# C-12_PWR_MEAS.net
KiCad netlist of a schematic drawn in Altium Designer
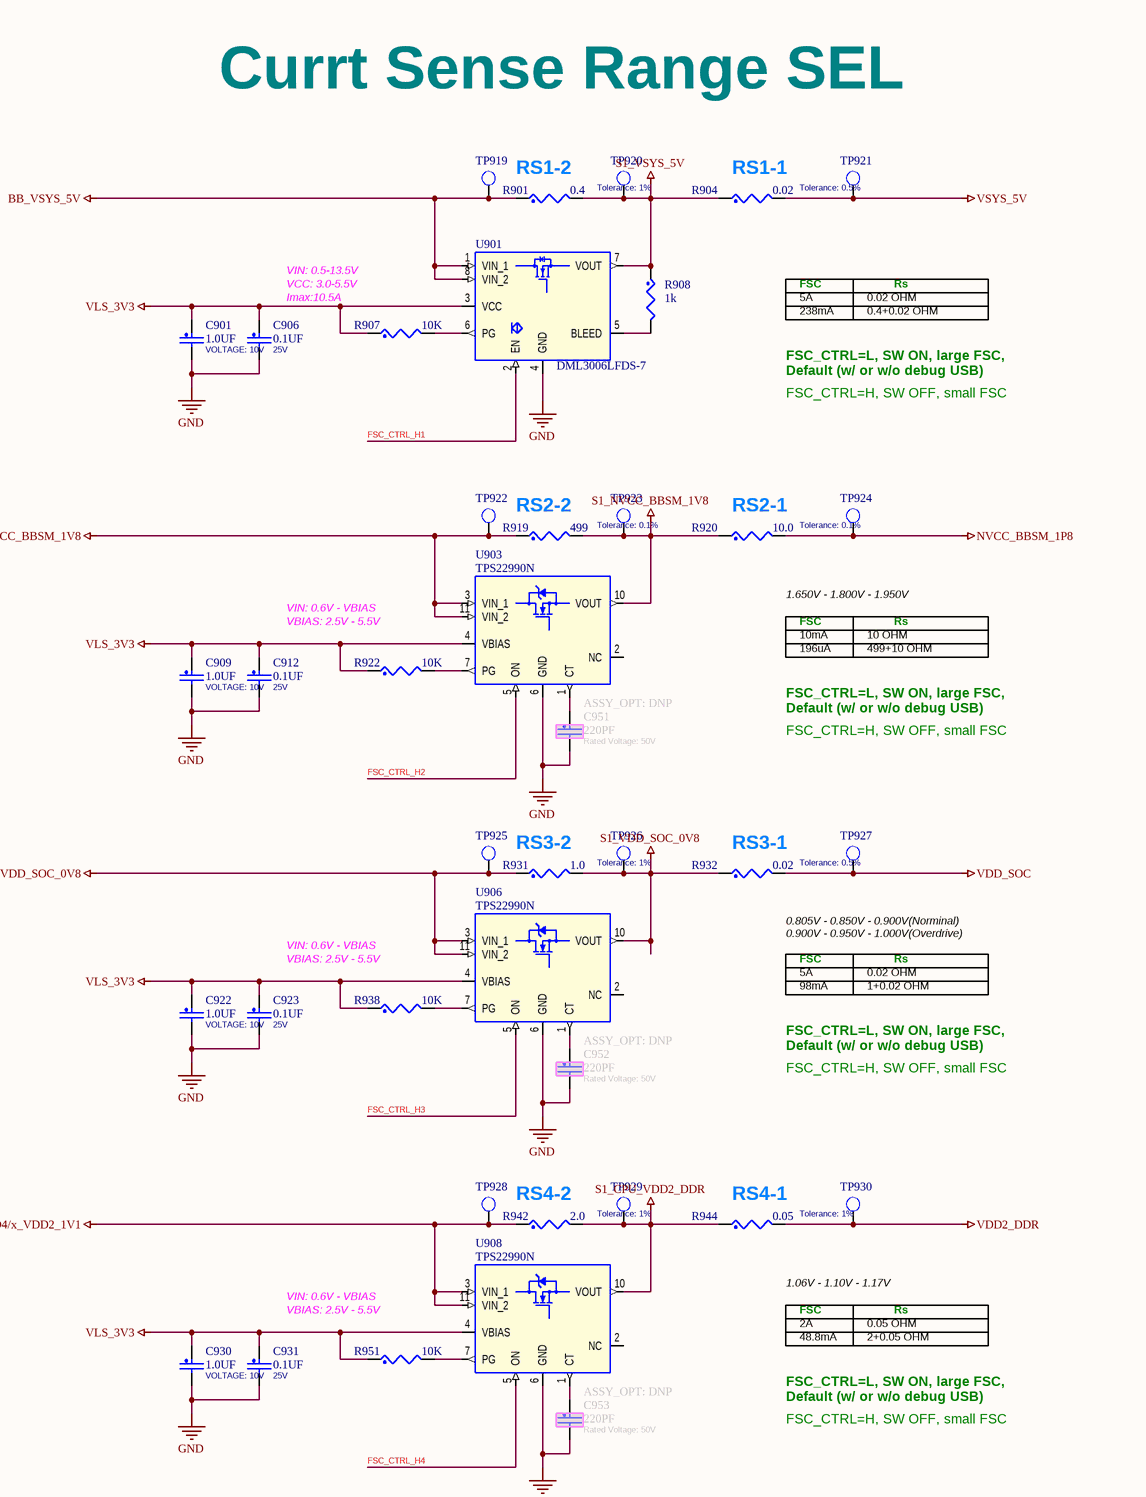
[diagram p0: C-12 PWR MEAS.SchDoc, top left]
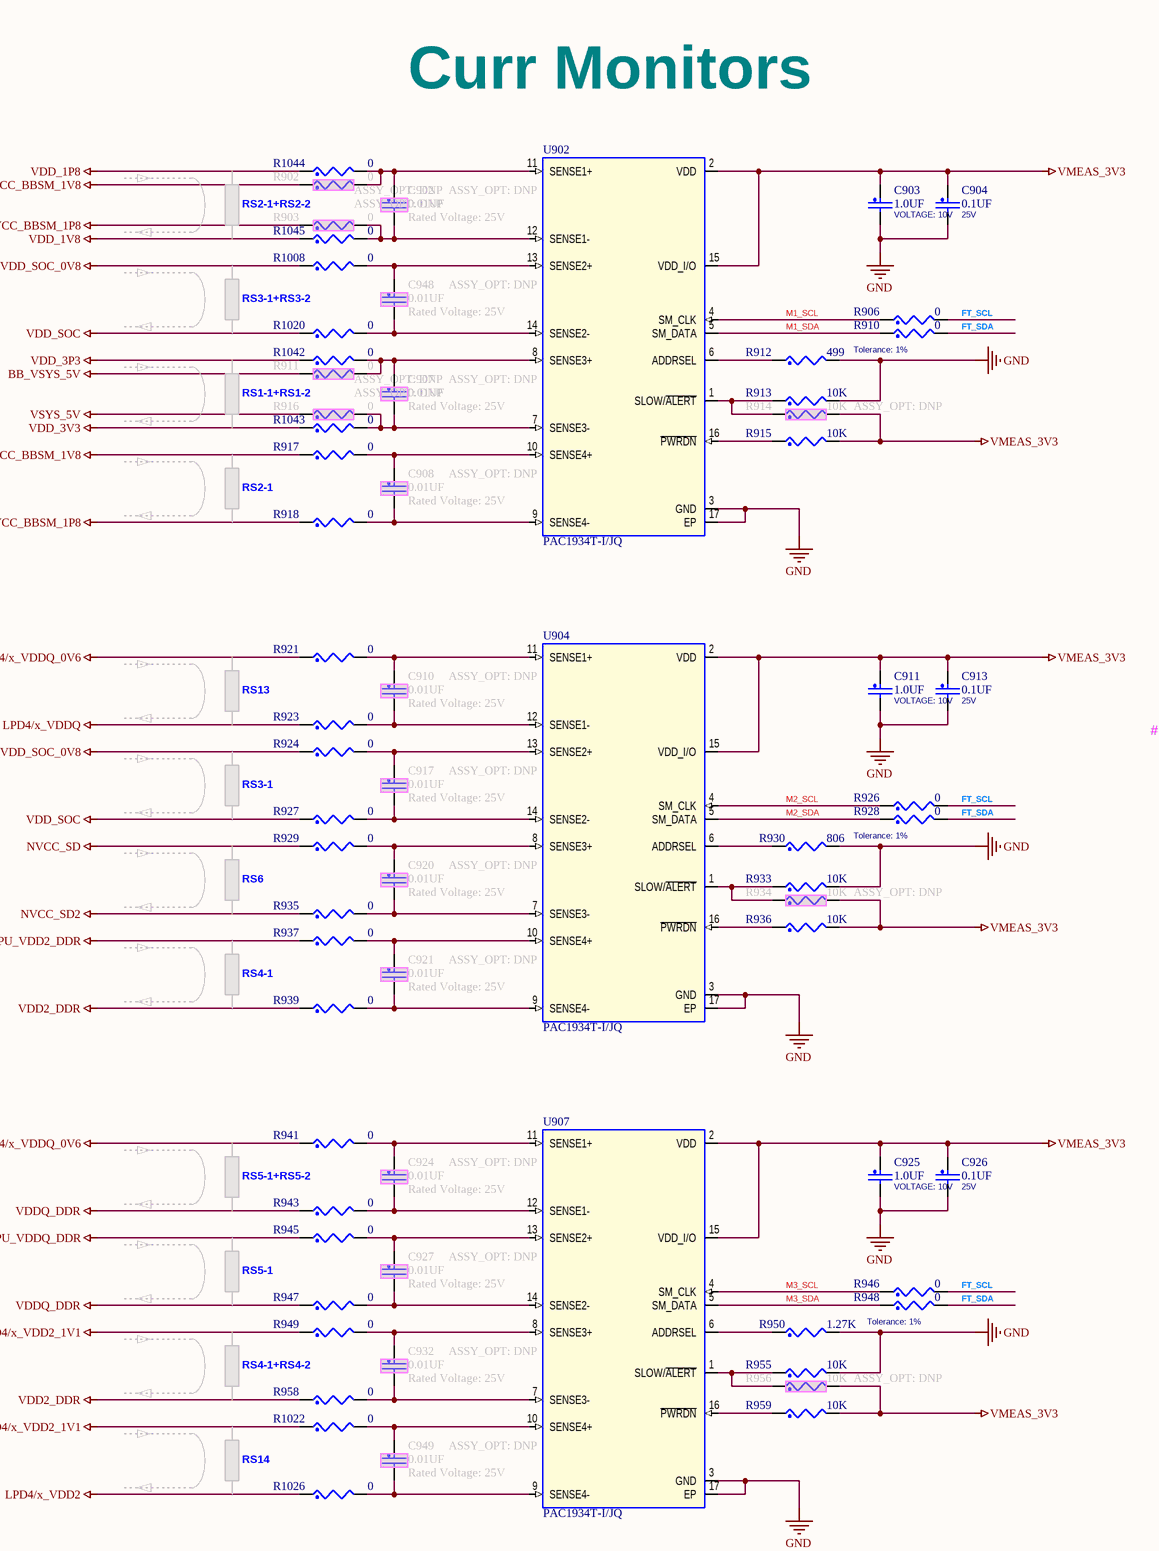
[diagram p1: C-12 PWR MEAS.SchDoc, top middle]
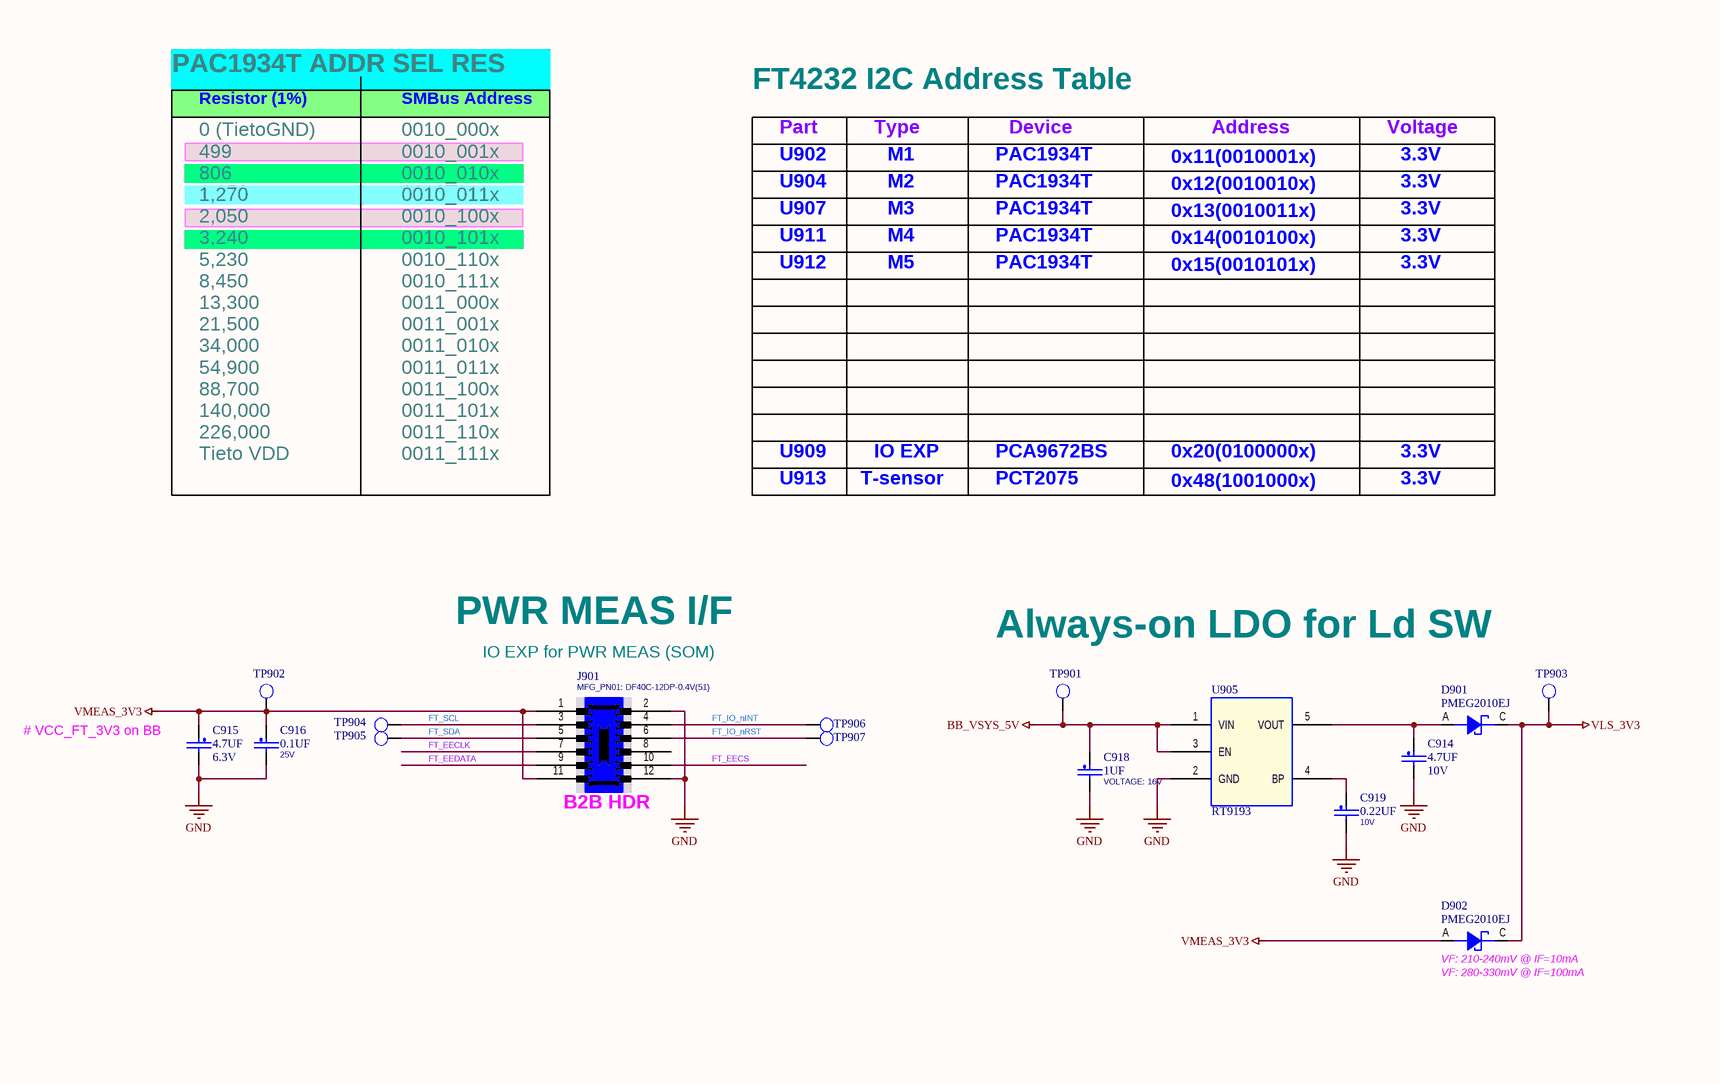
[diagram p2: C-12 PWR MEAS.SchDoc, top right]
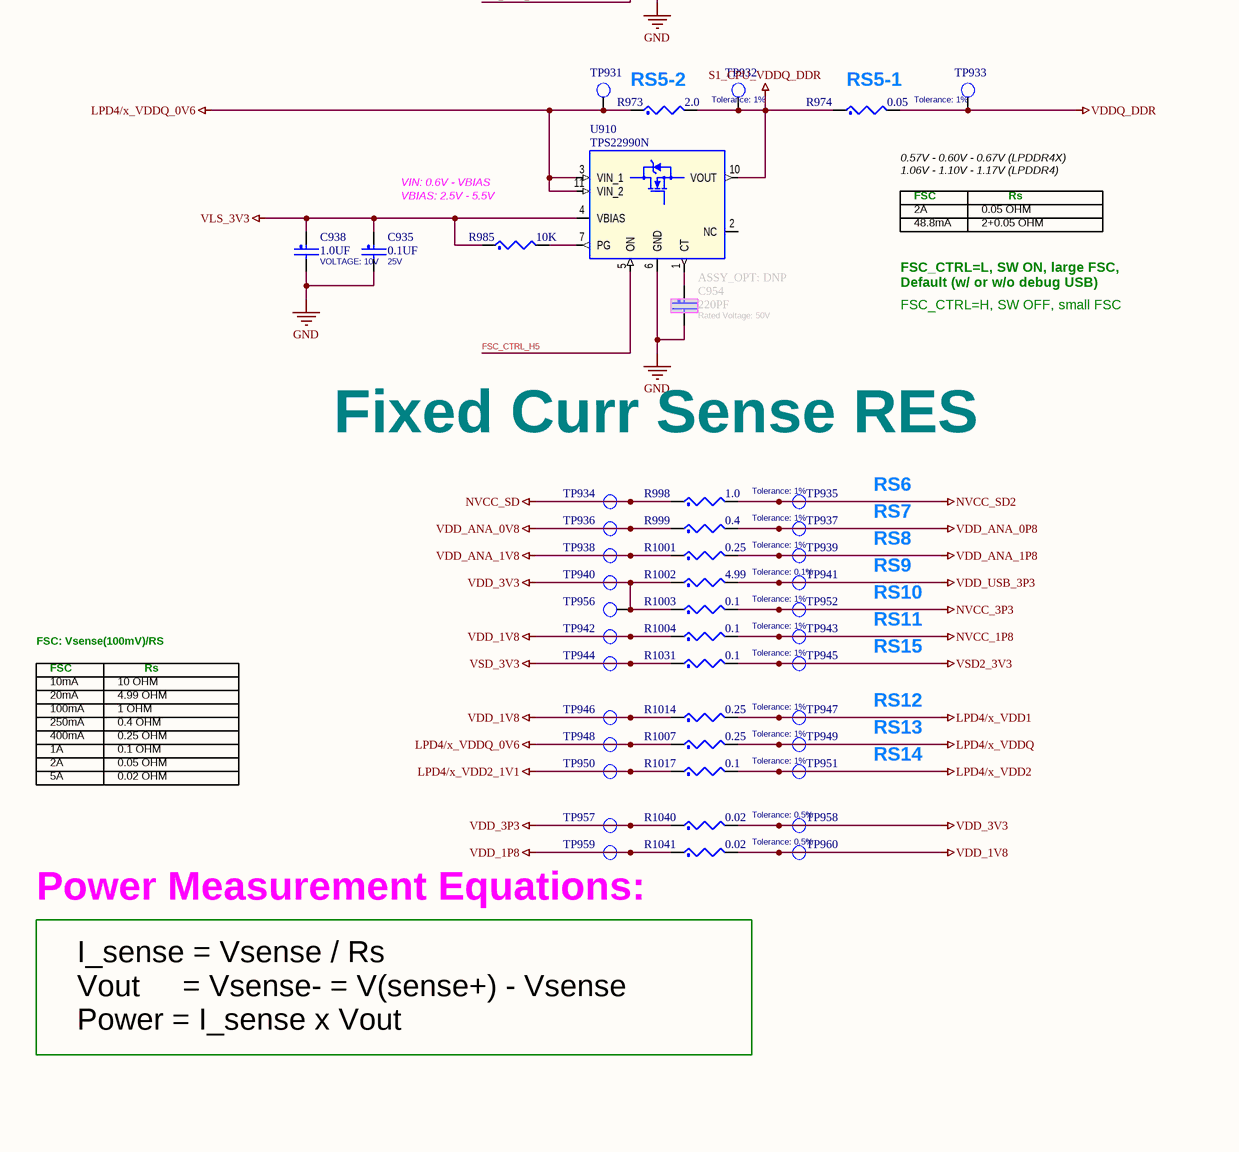
[diagram p3: C-12 PWR MEAS.SchDoc, bottom left]
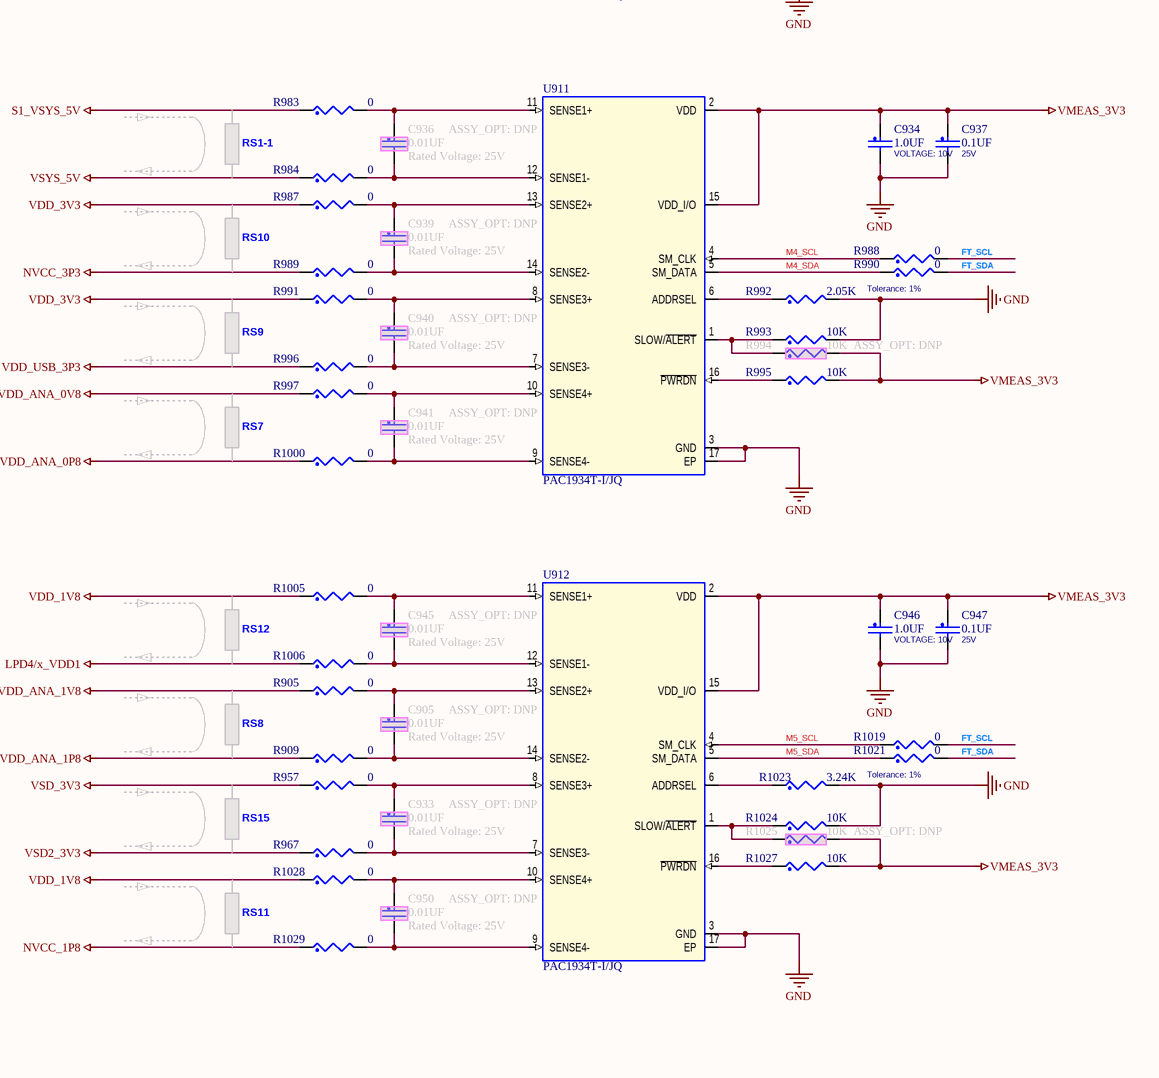
[diagram p4: C-12 PWR MEAS.SchDoc, bottom middle]
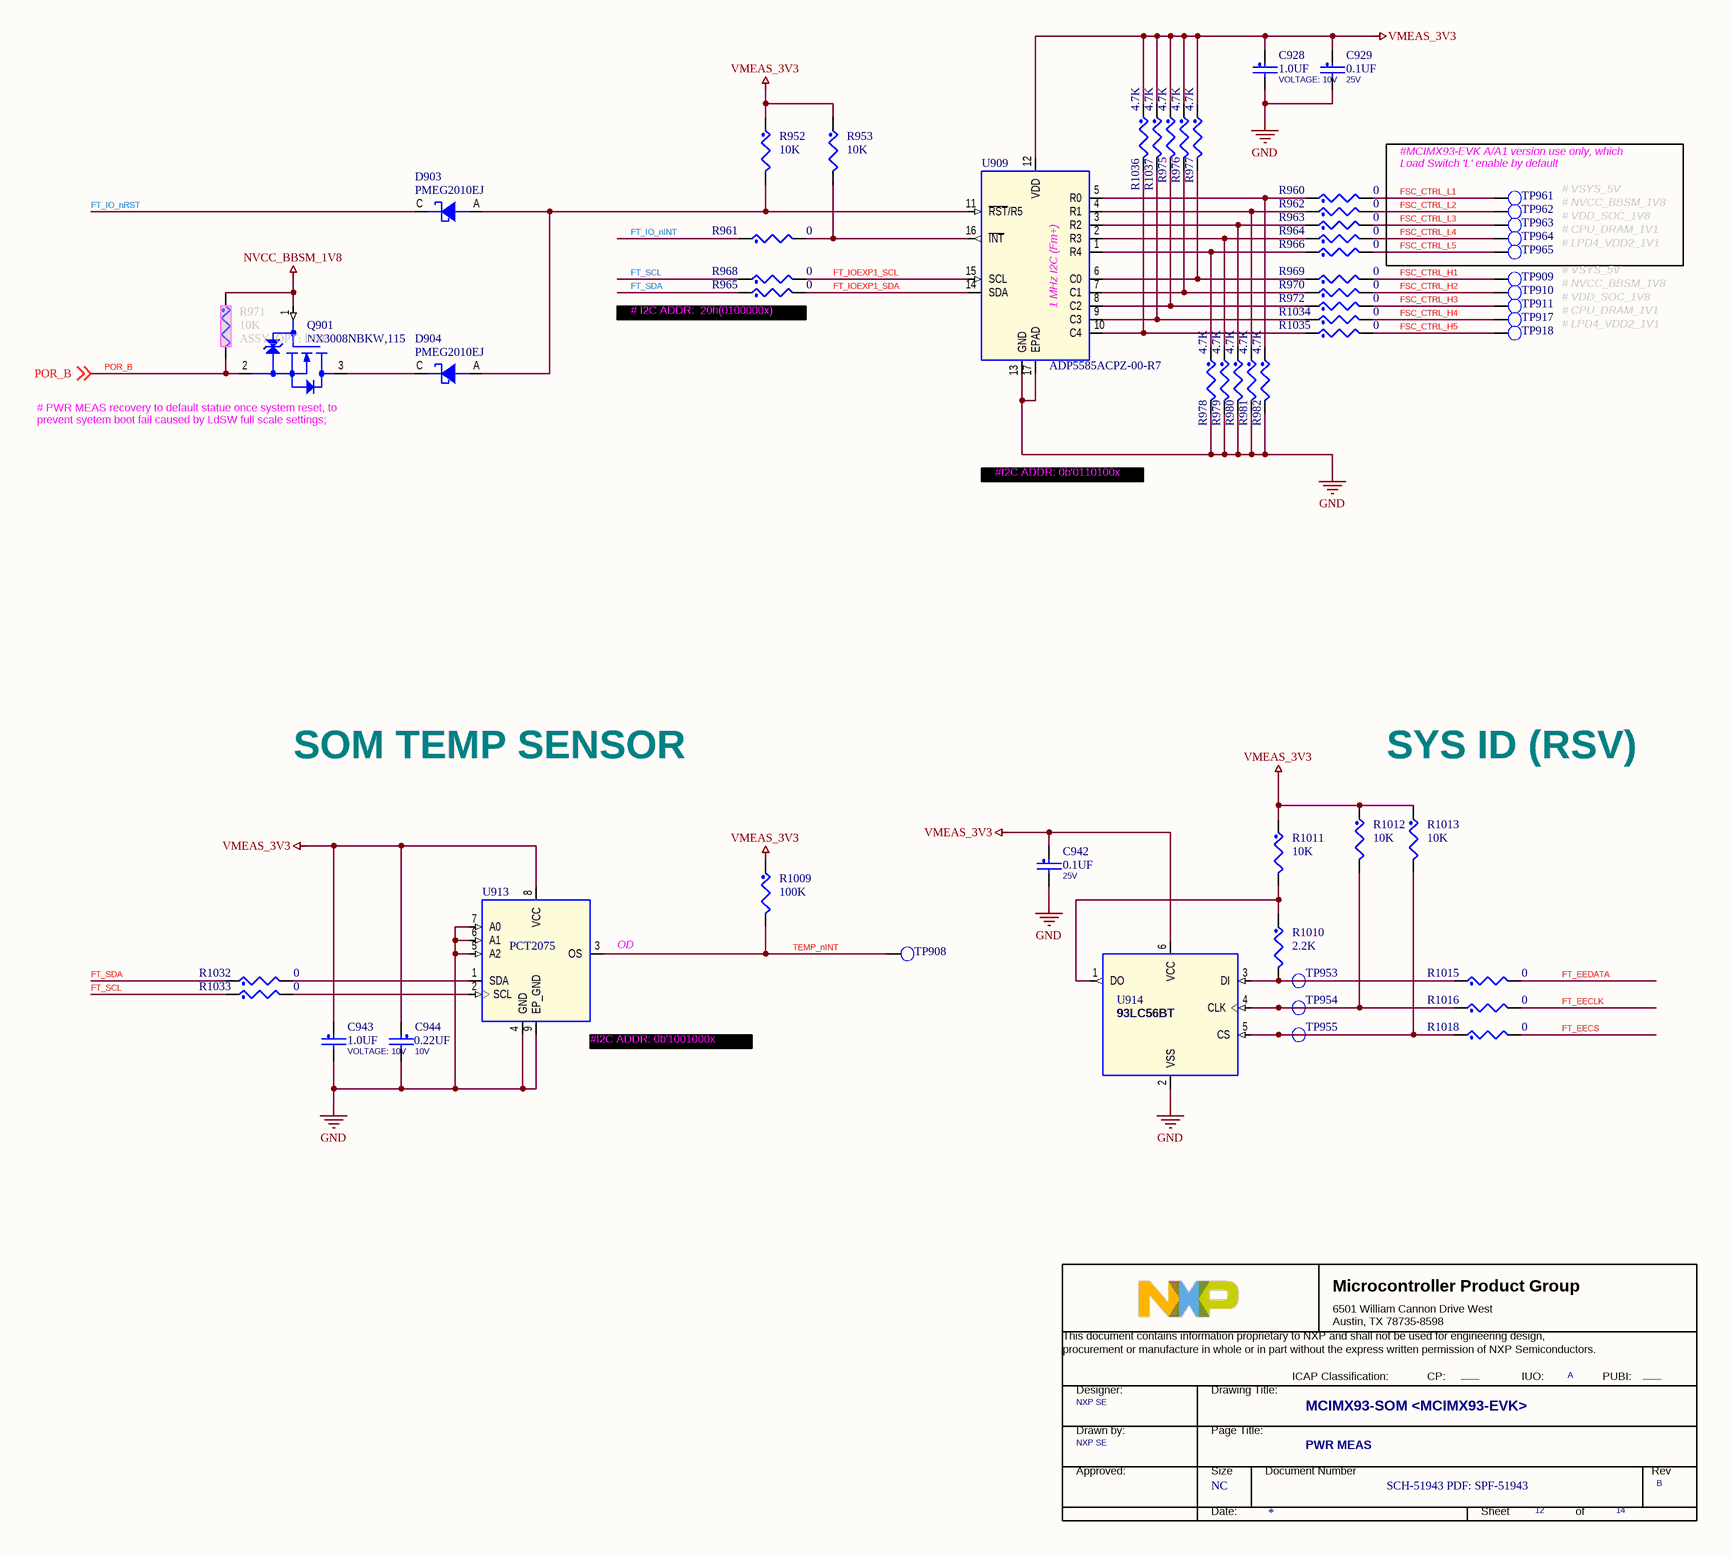
[diagram p5: C-12 PWR MEAS.SchDoc, bottom right]

(export (version "E")
  (design (tool "Eeschema 10.0.6"))
  (components
    (comp (ref "C901")
      (value "1.0UF")
      (footprint "0402_CC")
      (description "CAP CER 1.0UF 10V 10% X5R 0402")
      (fields (field (name "VOLTAGE") "10V"))
      (libsource (lib "*") (part "CAP_NP"))
    )
    (comp (ref "C902")
      (value "0.01UF")
      (footprint "CC0402_25")
      (description "CAP CER 0.01uF 25V 5% X7R 0402")
      (fields
        (field (name "ASSY_OPT") "DNP")
        (field (name "RATED VOLTAGE") "25V")
        (field (name "TOLERANCE") "5%")
      )
      (libsource (lib "*") (part "CAP_NP"))
    )
    (comp (ref "C903")
      (value "1.0UF")
      (footprint "0402_CC")
      (description "CAP CER 1.0UF 10V 10% X5R 0402")
      (fields (field (name "VOLTAGE") "10V"))
      (libsource (lib "*") (part "CAP_NP"))
    )
    (comp (ref "C904")
      (value "0.1UF")
      (footprint "0402_CC")
      (description "CAP CER 0.1UF 25V 10% X5R 0402")
      (fields (field (name "TOLERANCE") "10%") (field (name "VOLTAGE") "25V"))
      (libsource (lib "*") (part "CAP_NP"))
    )
    (comp (ref "C905")
      (value "0.01UF")
      (footprint "CC0402_25")
      (description "CAP CER 0.01uF 25V 5% X7R 0402")
      (fields
        (field (name "ASSY_OPT") "DNP")
        (field (name "RATED VOLTAGE") "25V")
        (field (name "TOLERANCE") "5%")
      )
      (libsource (lib "*") (part "CAP_NP"))
    )
    (comp (ref "C906")
      (value "0.1UF")
      (footprint "0402_CC")
      (description "CAP CER 0.1UF 25V 10% X5R 0402")
      (fields (field (name "TOLERANCE") "10%") (field (name "VOLTAGE") "25V"))
      (libsource (lib "*") (part "CAP_NP"))
    )
    (comp (ref "C907")
      (value "0.01UF")
      (footprint "CC0402_25")
      (description "CAP CER 0.01uF 25V 5% X7R 0402")
      (fields
        (field (name "ASSY_OPT") "DNP")
        (field (name "RATED VOLTAGE") "25V")
        (field (name "TOLERANCE") "5%")
      )
      (libsource (lib "*") (part "CAP_NP"))
    )
    (comp (ref "C908")
      (value "0.01UF")
      (footprint "CC0402_25")
      (description "CAP CER 0.01uF 25V 5% X7R 0402")
      (fields
        (field (name "ASSY_OPT") "DNP")
        (field (name "RATED VOLTAGE") "25V")
        (field (name "TOLERANCE") "5%")
      )
      (libsource (lib "*") (part "CAP_NP"))
    )
    (comp (ref "C909")
      (value "1.0UF")
      (footprint "0402_CC")
      (description "CAP CER 1.0UF 10V 10% X5R 0402")
      (fields (field (name "VOLTAGE") "10V"))
      (libsource (lib "*") (part "CAP_NP"))
    )
    (comp (ref "C910")
      (value "0.01UF")
      (footprint "CC0402_25")
      (description "CAP CER 0.01uF 25V 5% X7R 0402")
      (fields
        (field (name "ASSY_OPT") "DNP")
        (field (name "TOLERANCE") "5%")
        (field (name "RATED VOLTAGE") "25V")
      )
      (libsource (lib "*") (part "CAP_NP"))
    )
    (comp (ref "C911")
      (value "1.0UF")
      (footprint "0402_CC")
      (description "CAP CER 1.0UF 10V 10% X5R 0402")
      (fields (field (name "VOLTAGE") "10V"))
      (libsource (lib "*") (part "CAP_NP"))
    )
    (comp (ref "C912")
      (value "0.1UF")
      (footprint "0402_CC")
      (description "CAP CER 0.1UF 25V 10% X5R 0402")
      (fields (field (name "VOLTAGE") "25V") (field (name "TOLERANCE") "10%"))
      (libsource (lib "*") (part "CAP_NP"))
    )
    (comp (ref "C913")
      (value "0.1UF")
      (footprint "0402_CC")
      (description "CAP CER 0.1UF 25V 10% X5R 0402")
      (fields (field (name "VOLTAGE") "25V") (field (name "TOLERANCE") "10%"))
      (libsource (lib "*") (part "CAP_NP"))
    )
    (comp (ref "C914")
      (value "4.7UF")
      (footprint "cc0402_tol0p15")
      (description "CAP CER 4.7uF 10V 10% X5R 0402")
      (fields (field (name "TOLERANCE") "10%") (field (name "VOLTAGE") "10V"))
      (libsource (lib "*") (part "CAP_NP"))
    )
    (comp (ref "C915")
      (value "4.7UF")
      (footprint "cc0402_tol0p15")
      (description "CAP CER 4.7uF 10V 10% X5R 0402")
      (fields
        (field (name "VOLTAGE") "10V")
        (field (name "VOLTAGE RATING") "6.3V")
        (field (name "TOLERANCE") "10%")
      )
      (libsource (lib "*") (part "CAP_NP"))
    )
    (comp (ref "C916")
      (value "0.1UF")
      (footprint "0402_CC")
      (description "CAP CER 0.1UF 25V 10% X5R 0402")
      (fields (field (name "TOLERANCE") "10%") (field (name "VOLTAGE") "25V"))
      (libsource (lib "*") (part "CAP_NP"))
    )
    (comp (ref "C917")
      (value "0.01UF")
      (footprint "CC0402_25")
      (description "CAP CER 0.01uF 25V 5% X7R 0402")
      (fields
        (field (name "ASSY_OPT") "DNP")
        (field (name "TOLERANCE") "5%")
        (field (name "RATED VOLTAGE") "25V")
      )
      (libsource (lib "*") (part "CAP_NP"))
    )
    (comp (ref "C918")
      (value "1UF")
      (footprint "0402_CC")
      (description "CAP CER 1uF 16V 10% X5R 0402")
      (fields (field (name "VOLTAGE") "16V") (field (name "TOLERANCE") "10%"))
      (libsource (lib "*") (part "CAP_NP"))
    )
    (comp (ref "C919")
      (value "0.22UF")
      (footprint "0201_CC")
      (description "CAP CER 0.22UF 10V 20% X5R 0201")
      (fields (field (name "VOLTAGE") "10V") (field (name "TOLERANCE") "20%"))
      (libsource (lib "*") (part "CAP_NP"))
    )
    (comp (ref "C920")
      (value "0.01UF")
      (footprint "CC0402_25")
      (description "CAP CER 0.01uF 25V 5% X7R 0402")
      (fields
        (field (name "ASSY_OPT") "DNP")
        (field (name "TOLERANCE") "5%")
        (field (name "RATED VOLTAGE") "25V")
      )
      (libsource (lib "*") (part "CAP_NP"))
    )
    (comp (ref "C921")
      (value "0.01UF")
      (footprint "CC0402_25")
      (description "CAP CER 0.01uF 25V 5% X7R 0402")
      (fields
        (field (name "ASSY_OPT") "DNP")
        (field (name "TOLERANCE") "5%")
        (field (name "RATED VOLTAGE") "25V")
      )
      (libsource (lib "*") (part "CAP_NP"))
    )
    (comp (ref "C922")
      (value "1.0UF")
      (footprint "0402_CC")
      (description "CAP CER 1.0UF 10V 10% X5R 0402")
      (fields (field (name "VOLTAGE") "10V"))
      (libsource (lib "*") (part "CAP_NP"))
    )
    (comp (ref "C923")
      (value "0.1UF")
      (footprint "0402_CC")
      (description "CAP CER 0.1UF 25V 10% X5R 0402")
      (fields (field (name "VOLTAGE") "25V") (field (name "TOLERANCE") "10%"))
      (libsource (lib "*") (part "CAP_NP"))
    )
    (comp (ref "C924")
      (value "0.01UF")
      (footprint "CC0402_25")
      (description "CAP CER 0.01uF 25V 5% X7R 0402")
      (fields
        (field (name "ASSY_OPT") "DNP")
        (field (name "TOLERANCE") "5%")
        (field (name "RATED VOLTAGE") "25V")
      )
      (libsource (lib "*") (part "CAP_NP"))
    )
    (comp (ref "C925")
      (value "1.0UF")
      (footprint "0402_CC")
      (description "CAP CER 1.0UF 10V 10% X5R 0402")
      (fields (field (name "VOLTAGE") "10V"))
      (libsource (lib "*") (part "CAP_NP"))
    )
    (comp (ref "C926")
      (value "0.1UF")
      (footprint "0402_CC")
      (description "CAP CER 0.1UF 25V 10% X5R 0402")
      (fields (field (name "VOLTAGE") "25V") (field (name "TOLERANCE") "10%"))
      (libsource (lib "*") (part "CAP_NP"))
    )
    (comp (ref "C927")
      (value "0.01UF")
      (footprint "CC0402_25")
      (description "CAP CER 0.01uF 25V 5% X7R 0402")
      (fields
        (field (name "ASSY_OPT") "DNP")
        (field (name "TOLERANCE") "5%")
        (field (name "RATED VOLTAGE") "25V")
      )
      (libsource (lib "*") (part "CAP_NP"))
    )
    (comp (ref "C928")
      (value "1.0UF")
      (footprint "0402_CC")
      (description "CAP CER 1.0UF 10V 10% X5R 0402")
      (fields (field (name "VOLTAGE") "10V"))
      (libsource (lib "*") (part "CAP_NP"))
    )
    (comp (ref "C929")
      (value "0.1UF")
      (footprint "0402_CC")
      (description "CAP CER 0.1UF 25V 10% X5R 0402")
      (fields (field (name "VOLTAGE") "25V") (field (name "TOLERANCE") "10%"))
      (libsource (lib "*") (part "CAP_NP"))
    )
    (comp (ref "C930")
      (value "1.0UF")
      (footprint "0402_CC")
      (description "CAP CER 1.0UF 10V 10% X5R 0402")
      (fields (field (name "VOLTAGE") "10V"))
      (libsource (lib "*") (part "CAP_NP"))
    )
    (comp (ref "C931")
      (value "0.1UF")
      (footprint "0402_CC")
      (description "CAP CER 0.1UF 25V 10% X5R 0402")
      (fields (field (name "VOLTAGE") "25V") (field (name "TOLERANCE") "10%"))
      (libsource (lib "*") (part "CAP_NP"))
    )
    (comp (ref "C932")
      (value "0.01UF")
      (footprint "CC0402_25")
      (description "CAP CER 0.01uF 25V 5% X7R 0402")
      (fields
        (field (name "ASSY_OPT") "DNP")
        (field (name "TOLERANCE") "5%")
        (field (name "RATED VOLTAGE") "25V")
      )
      (libsource (lib "*") (part "CAP_NP"))
    )
    (comp (ref "C933")
      (value "0.01UF")
      (footprint "CC0402_25")
      (description "CAP CER 0.01uF 25V 5% X7R 0402")
      (fields
        (field (name "ASSY_OPT") "DNP")
        (field (name "TOLERANCE") "5%")
        (field (name "RATED VOLTAGE") "25V")
      )
      (libsource (lib "*") (part "CAP_NP"))
    )
    (comp (ref "C934")
      (value "1.0UF")
      (footprint "0402_CC")
      (description "CAP CER 1.0UF 10V 10% X5R 0402")
      (fields (field (name "VOLTAGE") "10V"))
      (libsource (lib "*") (part "CAP_NP"))
    )
    (comp (ref "C935")
      (value "0.1UF")
      (footprint "0402_CC")
      (description "CAP CER 0.1UF 25V 10% X5R 0402")
      (fields (field (name "VOLTAGE") "25V") (field (name "TOLERANCE") "10%"))
      (libsource (lib "*") (part "CAP_NP"))
    )
    (comp (ref "C936")
      (value "0.01UF")
      (footprint "CC0402_25")
      (description "CAP CER 0.01uF 25V 5% X7R 0402")
      (fields
        (field (name "ASSY_OPT") "DNP")
        (field (name "TOLERANCE") "5%")
        (field (name "RATED VOLTAGE") "25V")
      )
      (libsource (lib "*") (part "CAP_NP"))
    )
    (comp (ref "C937")
      (value "0.1UF")
      (footprint "0402_CC")
      (description "CAP CER 0.1UF 25V 10% X5R 0402")
      (fields (field (name "VOLTAGE") "25V") (field (name "TOLERANCE") "10%"))
      (libsource (lib "*") (part "CAP_NP"))
    )
    (comp (ref "C938")
      (value "1.0UF")
      (footprint "0402_CC")
      (description "CAP CER 1.0UF 10V 10% X5R 0402")
      (fields (field (name "VOLTAGE") "10V"))
      (libsource (lib "*") (part "CAP_NP"))
    )
    (comp (ref "C939")
      (value "0.01UF")
      (footprint "CC0402_25")
      (description "CAP CER 0.01uF 25V 5% X7R 0402")
      (fields
        (field (name "ASSY_OPT") "DNP")
        (field (name "TOLERANCE") "5%")
        (field (name "RATED VOLTAGE") "25V")
      )
      (libsource (lib "*") (part "CAP_NP"))
    )
    (comp (ref "C940")
      (value "0.01UF")
      (footprint "CC0402_25")
      (description "CAP CER 0.01uF 25V 5% X7R 0402")
      (fields
        (field (name "ASSY_OPT") "DNP")
        (field (name "TOLERANCE") "5%")
        (field (name "RATED VOLTAGE") "25V")
      )
      (libsource (lib "*") (part "CAP_NP"))
    )
    (comp (ref "C941")
      (value "0.01UF")
      (footprint "CC0402_25")
      (description "CAP CER 0.01uF 25V 5% X7R 0402")
      (fields
        (field (name "ASSY_OPT") "DNP")
        (field (name "TOLERANCE") "5%")
        (field (name "RATED VOLTAGE") "25V")
      )
      (libsource (lib "*") (part "CAP_NP"))
    )
    (comp (ref "C942")
      (value "0.1UF")
      (footprint "0402_CC")
      (description "CAP CER 0.1UF 25V 10% X5R 0402")
      (fields (field (name "TOLERANCE") "10%") (field (name "VOLTAGE") "25V"))
      (libsource (lib "*") (part "CAP_NP"))
    )
    (comp (ref "C943")
      (value "1.0UF")
      (footprint "0402_CC")
      (description "CAP CER 1.0UF 10V 10% X5R 0402")
      (fields (field (name "VOLTAGE") "10V"))
      (libsource (lib "*") (part "CAP_NP"))
    )
    (comp (ref "C944")
      (value "0.22UF")
      (footprint "0201_CC")
      (description "CAP CER 0.22UF 10V 20% X5R 0201")
      (fields (field (name "TOLERANCE") "20%") (field (name "VOLTAGE") "10V"))
      (libsource (lib "*") (part "CAP_NP"))
    )
    (comp (ref "C945")
      (value "0.01UF")
      (footprint "CC0402_25")
      (description "CAP CER 0.01uF 25V 5% X7R 0402")
      (fields
        (field (name "ASSY_OPT") "DNP")
        (field (name "TOLERANCE") "5%")
        (field (name "RATED VOLTAGE") "25V")
      )
      (libsource (lib "*") (part "CAP_NP"))
    )
    (comp (ref "C946")
      (value "1.0UF")
      (footprint "0402_CC")
      (description "CAP CER 1.0UF 10V 10% X5R 0402")
      (fields (field (name "VOLTAGE") "10V"))
      (libsource (lib "*") (part "CAP_NP"))
    )
    (comp (ref "C947")
      (value "0.1UF")
      (footprint "0402_CC")
      (description "CAP CER 0.1UF 25V 10% X5R 0402")
      (fields (field (name "VOLTAGE") "25V") (field (name "TOLERANCE") "10%"))
      (libsource (lib "*") (part "CAP_NP"))
    )
    (comp (ref "C948")
      (value "0.01UF")
      (footprint "CC0402_25")
      (description "CAP CER 0.01uF 25V 5% X7R 0402")
      (fields
        (field (name "ASSY_OPT") "DNP")
        (field (name "TOLERANCE") "5%")
        (field (name "RATED VOLTAGE") "25V")
      )
      (libsource (lib "*") (part "CAP_NP"))
    )
    (comp (ref "C949")
      (value "0.01UF")
      (footprint "CC0402_25")
      (description "CAP CER 0.01uF 25V 5% X7R 0402")
      (fields
        (field (name "ASSY_OPT") "DNP")
        (field (name "TOLERANCE") "5%")
        (field (name "RATED VOLTAGE") "25V")
      )
      (libsource (lib "*") (part "CAP_NP"))
    )
    (comp (ref "C950")
      (value "0.01UF")
      (footprint "CC0402_25")
      (description "CAP CER 0.01uF 25V 5% X7R 0402")
      (fields
        (field (name "ASSY_OPT") "DNP")
        (field (name "TOLERANCE") "5%")
        (field (name "RATED VOLTAGE") "25V")
      )
      (libsource (lib "*") (part "CAP_NP"))
    )
    (comp (ref "C951")
      (value "220PF")
      (footprint "0402_CC")
      (description "CAP CER 220PF 50V 5% C0G 0402")
      (fields
        (field (name "ASSY_OPT") "DNP")
        (field (name "RATED VOLTAGE") "50V")
        (field (name "TOLERANCE") "5%")
      )
      (libsource (lib "*") (part "CAP_NP"))
    )
    (comp (ref "C952")
      (value "220PF")
      (footprint "0402_CC")
      (description "CAP CER 220PF 50V 5% C0G 0402")
      (fields
        (field (name "ASSY_OPT") "DNP")
        (field (name "RATED VOLTAGE") "50V")
        (field (name "TOLERANCE") "5%")
      )
      (libsource (lib "*") (part "CAP_NP"))
    )
    (comp (ref "C953")
      (value "220PF")
      (footprint "0402_CC")
      (description "CAP CER 220PF 50V 5% C0G 0402")
      (fields
        (field (name "ASSY_OPT") "DNP")
        (field (name "RATED VOLTAGE") "50V")
        (field (name "TOLERANCE") "5%")
      )
      (libsource (lib "*") (part "CAP_NP"))
    )
    (comp (ref "C954")
      (value "220PF")
      (footprint "0402_CC")
      (description "CAP CER 220PF 50V 5% C0G 0402")
      (fields
        (field (name "ASSY_OPT") "DNP")
        (field (name "RATED VOLTAGE") "50V")
        (field (name "TOLERANCE") "5%")
      )
      (libsource (lib "*") (part "CAP_NP"))
    )
    (comp (ref "D901")
      (value "PMEG2010EJ")
      (footprint "sod323")
      (description "DIODE SCH SW 1A 20V AEC-Q101 SOD323")
      (fields (field (name "VOLTAGE") "20V"))
      (libsource (lib "*") (part "DIODE_SCHTKY"))
    )
    (comp (ref "D902")
      (value "PMEG2010EJ")
      (footprint "sod323")
      (description "DIODE SCH SW 1A 20V AEC-Q101 SOD323")
      (fields (field (name "VOLTAGE") "20V"))
      (libsource (lib "*") (part "DIODE_SCHTKY"))
    )
    (comp (ref "D903")
      (value "PMEG2010EJ")
      (footprint "sod323")
      (description "DIODE SCH SW 1A 20V AEC-Q101 SOD323")
      (fields (field (name "VOLTAGE") "20V"))
      (libsource (lib "*") (part "DIODE_SCHTKY"))
    )
    (comp (ref "D904")
      (value "PMEG2010EJ")
      (footprint "sod323")
      (description "DIODE SCH SW 1A 20V AEC-Q101 SOD323")
      (fields (field (name "VOLTAGE") "20V"))
      (libsource (lib "*") (part "DIODE_SCHTKY"))
    )
    (comp (ref "J901")
      (value "CON 2X6")
      (footprint "con12_0p4_4p12x2p05_sm")
      (description "CON 2X6 PLUG SHRD SMT 0.4MM SP 51H AU")
      (fields (field (name "MFG_PN01") "DF40C-12DP-0.4V(51)"))
      (libsource (lib "*") (part "CONN_HDR_6X2_A"))
    )
    (comp (ref "Q901")
      (value "NX3008NBKW,115")
      (footprint "sc70_3")
      (description "TRAN NMOS SW 30V 350mA AEC-Q101 SC-70")
      (libsource (lib "*") (part "NX3008NBKW_SOT323"))
    )
    (comp (ref "R901")
      (value "0.4")
      (footprint "RC0603_OV")
      (description "RES MF 0.4 OHM 1/10W 1% AEC-Q200 0603")
      (fields (field (name "TOLERANCE") "1%"))
      (libsource (lib "*") (part "RES"))
    )
    (comp (ref "R902")
      (value "0")
      (footprint "0402_CC")
      (description "RES MF ZERO OHM 1/16W 5% 0402")
      (fields
        (field (name "ASSY_OPT") "DNP")
        (field (name "VOLTAGE") "1/16W")
        (field (name "TOLERANCE") "5%")
      )
      (libsource (lib "*") (part "RES"))
    )
    (comp (ref "R903")
      (value "0")
      (footprint "0402_CC")
      (description "RES MF ZERO OHM 1/16W 5% 0402")
      (fields
        (field (name "ASSY_OPT") "DNP")
        (field (name "VOLTAGE") "1/16W")
        (field (name "TOLERANCE") "5%")
      )
      (libsource (lib "*") (part "RES"))
    )
    (comp (ref "R904")
      (value "0.02")
      (footprint "RC0805_OV")
      (description "RES MF 0.02OHM 1/4W 0.5% 0805")
      (fields (field (name "TOLERANCE") "0.5%"))
      (libsource (lib "*") (part "RES"))
    )
    (comp (ref "R905")
      (value "0")
      (footprint "0402_CC")
      (description "RES MF ZERO OHM 1/16W 5% 0402")
      (fields (field (name "VOLTAGE") "1/16W") (field (name "TOLERANCE") "5%"))
      (libsource (lib "*") (part "RES"))
    )
    (comp (ref "R906")
      (value "0")
      (footprint "0201_CC")
      (description "RES MF ZERO OHM 1/20W -- 0201")
      (libsource (lib "*") (part "RES"))
    )
    (comp (ref "R907")
      (value "10K")
      (footprint "0402_CC")
      (description "RES MF 10K 1/16W 5% 0402")
      (fields (field (name "TOLERANCE") "5%"))
      (libsource (lib "*") (part "RES"))
    )
    (comp (ref "R908")
      (value "1k")
      (footprint "RC0603_OV")
      (description "RES MF 1.0K 1/10W 5% 0603")
      (fields (field (name "TOLERANCE") "5%"))
      (libsource (lib "*") (part "RES"))
    )
    (comp (ref "R909")
      (value "0")
      (footprint "0402_CC")
      (description "RES MF ZERO OHM 1/16W 5% 0402")
      (fields (field (name "VOLTAGE") "1/16W") (field (name "TOLERANCE") "5%"))
      (libsource (lib "*") (part "RES"))
    )
    (comp (ref "R910")
      (value "0")
      (footprint "0201_CC")
      (description "RES MF ZERO OHM 1/20W -- 0201")
      (libsource (lib "*") (part "RES"))
    )
    (comp (ref "R911")
      (value "0")
      (footprint "0402_CC")
      (description "RES MF ZERO OHM 1/16W 5% 0402")
      (fields
        (field (name "ASSY_OPT") "DNP")
        (field (name "TOLERANCE") "5%")
        (field (name "VOLTAGE") "1/16W")
      )
      (libsource (lib "*") (part "RES"))
    )
    (comp (ref "R912")
      (value "499")
      (footprint "RC0402_25")
      (description "RES MF 499 OHM 1/16W 1% 0402")
      (fields (field (name "TOLERANCE") "1%"))
      (libsource (lib "*") (part "RES"))
    )
    (comp (ref "R913")
      (value "10K")
      (footprint "0402_CC")
      (description "RES MF 10K 1/16W 5% 0402")
      (fields (field (name "TOLERANCE") "5%"))
      (libsource (lib "*") (part "RES"))
    )
    (comp (ref "R914")
      (value "10K")
      (footprint "0402_CC")
      (description "RES MF 10K 1/16W 5% 0402")
      (fields (field (name "ASSY_OPT") "DNP") (field (name "TOLERANCE") "5%"))
      (libsource (lib "*") (part "RES"))
    )
    (comp (ref "R915")
      (value "10K")
      (footprint "0402_CC")
      (description "RES MF 10K 1/16W 5% 0402")
      (fields (field (name "TOLERANCE") "5%"))
      (libsource (lib "*") (part "RES"))
    )
    (comp (ref "R916")
      (value "0")
      (footprint "0402_CC")
      (description "RES MF ZERO OHM 1/16W 5% 0402")
      (fields
        (field (name "ASSY_OPT") "DNP")
        (field (name "VOLTAGE") "1/16W")
        (field (name "TOLERANCE") "5%")
      )
      (libsource (lib "*") (part "RES"))
    )
    (comp (ref "R917")
      (value "0")
      (footprint "0402_CC")
      (description "RES MF ZERO OHM 1/16W 5% 0402")
      (fields (field (name "VOLTAGE") "1/16W") (field (name "TOLERANCE") "5%"))
      (libsource (lib "*") (part "RES"))
    )
    (comp (ref "R918")
      (value "0")
      (footprint "0402_CC")
      (description "RES MF ZERO OHM 1/16W 5% 0402")
      (fields (field (name "VOLTAGE") "1/16W") (field (name "TOLERANCE") "5%"))
      (libsource (lib "*") (part "RES"))
    )
    (comp (ref "R919")
      (value "499")
      (footprint "RC0603_OV")
      (description "RES MF 499 OHM 1/10W 0.1% AEC-Q200 0603")
      (fields (field (name "TOLERANCE") "0.1%"))
      (libsource (lib "*") (part "RES"))
    )
    (comp (ref "R920")
      (value "10.0")
      (footprint "RC0603_OV")
      (description "RES MF 10 OHM 1/16W 0.1% 0603")
      (fields (field (name "TOLERANCE") "0.1%"))
      (libsource (lib "*") (part "RES"))
    )
    (comp (ref "R921")
      (value "0")
      (footprint "0402_CC")
      (description "RES MF ZERO OHM 1/16W 5% 0402")
      (fields (field (name "TOLERANCE") "5%") (field (name "VOLTAGE") "1/16W"))
      (libsource (lib "*") (part "RES"))
    )
    (comp (ref "R922")
      (value "10K")
      (footprint "0402_CC")
      (description "RES MF 10K 1/16W 5% 0402")
      (fields (field (name "TOLERANCE") "5%"))
      (libsource (lib "*") (part "RES"))
    )
    (comp (ref "R923")
      (value "0")
      (footprint "0402_CC")
      (description "RES MF ZERO OHM 1/16W 5% 0402")
      (fields (field (name "TOLERANCE") "5%") (field (name "VOLTAGE") "1/16W"))
      (libsource (lib "*") (part "RES"))
    )
    (comp (ref "R924")
      (value "0")
      (footprint "0402_CC")
      (description "RES MF ZERO OHM 1/16W 5% 0402")
      (fields (field (name "TOLERANCE") "5%") (field (name "VOLTAGE") "1/16W"))
      (libsource (lib "*") (part "RES"))
    )
    (comp (ref "R926")
      (value "0")
      (footprint "0201_CC")
      (description "RES MF ZERO OHM 1/20W -- 0201")
      (libsource (lib "*") (part "RES"))
    )
    (comp (ref "R927")
      (value "0")
      (footprint "0402_CC")
      (description "RES MF ZERO OHM 1/16W 5% 0402")
      (fields (field (name "TOLERANCE") "5%") (field (name "VOLTAGE") "1/16W"))
      (libsource (lib "*") (part "RES"))
    )
    (comp (ref "R928")
      (value "0")
      (footprint "0201_CC")
      (description "RES MF ZERO OHM 1/20W -- 0201")
      (libsource (lib "*") (part "RES"))
    )
    (comp (ref "R929")
      (value "0")
      (footprint "0402_CC")
      (description "RES MF ZERO OHM 1/16W 5% 0402")
      (fields (field (name "TOLERANCE") "5%") (field (name "VOLTAGE") "1/16W"))
      (libsource (lib "*") (part "RES"))
    )
    (comp (ref "R930")
      (value "806")
      (footprint "RC0402_25")
      (description "RES TF 806 OHM 1% 1/10W AEC-Q200 0402")
      (fields (field (name "TOLERANCE") "1%"))
      (libsource (lib "*") (part "RES"))
    )
    (comp (ref "R931")
      (value "1.0")
      (footprint "RC0603_OV")
      (description "RES MF 1.00 OHM 1/10W 1% 0603")
      (fields (field (name "TOLERANCE") "1%"))
      (libsource (lib "*") (part "RES"))
    )
    (comp (ref "R932")
      (value "0.02")
      (footprint "RC0805_OV")
      (description "RES MF 0.02OHM 1/4W 0.5% 0805")
      (fields (field (name "TOLERANCE") "0.5%"))
      (libsource (lib "*") (part "RES"))
    )
    (comp (ref "R933")
      (value "10K")
      (footprint "0402_CC")
      (description "RES MF 10K 1/16W 5% 0402")
      (fields (field (name "TOLERANCE") "5%"))
      (libsource (lib "*") (part "RES"))
    )
    (comp (ref "R934")
      (value "10K")
      (footprint "0402_CC")
      (description "RES MF 10K 1/16W 5% 0402")
      (fields (field (name "ASSY_OPT") "DNP") (field (name "TOLERANCE") "5%"))
      (libsource (lib "*") (part "RES"))
    )
    (comp (ref "R935")
      (value "0")
      (footprint "0402_CC")
      (description "RES MF ZERO OHM 1/16W 5% 0402")
      (fields (field (name "TOLERANCE") "5%") (field (name "VOLTAGE") "1/16W"))
      (libsource (lib "*") (part "RES"))
    )
    (comp (ref "R936")
      (value "10K")
      (footprint "0402_CC")
      (description "RES MF 10K 1/16W 5% 0402")
      (fields (field (name "TOLERANCE") "5%"))
      (libsource (lib "*") (part "RES"))
    )
    (comp (ref "R937")
      (value "0")
      (footprint "0402_CC")
      (description "RES MF ZERO OHM 1/16W 5% 0402")
      (fields (field (name "TOLERANCE") "5%") (field (name "VOLTAGE") "1/16W"))
      (libsource (lib "*") (part "RES"))
    )
    (comp (ref "R938")
      (value "10K")
      (footprint "0402_CC")
      (description "RES MF 10K 1/16W 5% 0402")
      (fields (field (name "TOLERANCE") "5%"))
      (libsource (lib "*") (part "RES"))
    )
    (comp (ref "R939")
      (value "0")
      (footprint "0402_CC")
      (description "RES MF ZERO OHM 1/16W 5% 0402")
      (fields (field (name "TOLERANCE") "5%") (field (name "VOLTAGE") "1/16W"))
      (libsource (lib "*") (part "RES"))
    )
    (comp (ref "R941")
      (value "0")
      (footprint "0402_CC")
      (description "RES MF ZERO OHM 1/16W 5% 0402")
      (fields (field (name "TOLERANCE") "5%") (field (name "VOLTAGE") "1/16W"))
      (libsource (lib "*") (part "RES"))
    )
    (comp (ref "R942")
      (value "2.0")
      (footprint "RC0603_OV")
      (description "RES MF 2.0 OHM 1/8W 1% AEC-Q200 0603")
      (fields (field (name "TOLERANCE") "1%"))
      (libsource (lib "*") (part "RES"))
    )
    (comp (ref "R943")
      (value "0")
      (footprint "0402_CC")
      (description "RES MF ZERO OHM 1/16W 5% 0402")
      (fields (field (name "TOLERANCE") "5%") (field (name "VOLTAGE") "1/16W"))
      (libsource (lib "*") (part "RES"))
    )
    (comp (ref "R944")
      (value "0.05")
      (footprint "RC0805_OV")
      (description "RES MF 0.05OHM 1/4W 1% 0805")
      (fields (field (name "TOLERANCE") "1%"))
      (libsource (lib "*") (part "RES"))
    )
    (comp (ref "R945")
      (value "0")
      (footprint "0402_CC")
      (description "RES MF ZERO OHM 1/16W 5% 0402")
      (fields (field (name "TOLERANCE") "5%") (field (name "VOLTAGE") "1/16W"))
      (libsource (lib "*") (part "RES"))
    )
    (comp (ref "R946")
      (value "0")
      (footprint "0201_CC")
      (description "RES MF ZERO OHM 1/20W -- 0201")
      (libsource (lib "*") (part "RES"))
    )
    (comp (ref "R947")
      (value "0")
      (footprint "0402_CC")
      (description "RES MF ZERO OHM 1/16W 5% 0402")
      (fields (field (name "TOLERANCE") "5%") (field (name "VOLTAGE") "1/16W"))
      (libsource (lib "*") (part "RES"))
    )
    (comp (ref "R948")
      (value "0")
      (footprint "0201_CC")
      (description "RES MF ZERO OHM 1/20W -- 0201")
      (libsource (lib "*") (part "RES"))
    )
    (comp (ref "R949")
      (value "0")
      (footprint "0402_CC")
      (description "RES MF ZERO OHM 1/16W 5% 0402")
      (fields (field (name "TOLERANCE") "5%") (field (name "VOLTAGE") "1/16W"))
      (libsource (lib "*") (part "RES"))
    )
    (comp (ref "R950")
      (value "1.27K")
      (footprint "RC0402_25")
      (description "RES MF 1.27K  1/10W 1% AEC-Q200 0402")
      (fields (field (name "TOLERANCE") "1%") (field (name "VOLTAGE") "50V"))
      (libsource (lib "*") (part "RES"))
    )
    (comp (ref "R951")
      (value "10K")
      (footprint "0402_CC")
      (description "RES MF 10K 1/16W 5% 0402")
      (fields (field (name "TOLERANCE") "5%"))
      (libsource (lib "*") (part "RES"))
    )
    (comp (ref "R952")
      (value "10K")
      (footprint "0402_CC")
      (description "RES MF 10K 1/16W 5% 0402")
      (fields (field (name "TOLERANCE") "5%"))
      (libsource (lib "*") (part "RES"))
    )
    (comp (ref "R953")
      (value "10K")
      (footprint "0402_CC")
      (description "RES MF 10K 1/16W 5% 0402")
      (fields (field (name "TOLERANCE") "5%"))
      (libsource (lib "*") (part "RES"))
    )
    (comp (ref "R955")
      (value "10K")
      (footprint "0402_CC")
      (description "RES MF 10K 1/16W 5% 0402")
      (fields (field (name "TOLERANCE") "5%"))
      (libsource (lib "*") (part "RES"))
    )
    (comp (ref "R956")
      (value "10K")
      (footprint "0402_CC")
      (description "RES MF 10K 1/16W 5% 0402")
      (fields (field (name "ASSY_OPT") "DNP") (field (name "TOLERANCE") "5%"))
      (libsource (lib "*") (part "RES"))
    )
    (comp (ref "R957")
      (value "0")
      (footprint "0402_CC")
      (description "RES MF ZERO OHM 1/16W 5% 0402")
      (fields (field (name "TOLERANCE") "5%") (field (name "VOLTAGE") "1/16W"))
      (libsource (lib "*") (part "RES"))
    )
    (comp (ref "R958")
      (value "0")
      (footprint "0402_CC")
      (description "RES MF ZERO OHM 1/16W 5% 0402")
      (fields (field (name "TOLERANCE") "5%") (field (name "VOLTAGE") "1/16W"))
      (libsource (lib "*") (part "RES"))
    )
    (comp (ref "R959")
      (value "10K")
      (footprint "0402_CC")
      (description "RES MF 10K 1/16W 5% 0402")
      (fields (field (name "TOLERANCE") "5%"))
      (libsource (lib "*") (part "RES"))
    )
    (comp (ref "R960")
      (value "0")
      (footprint "0402_CC")
      (description "RES MF ZERO OHM 1/16W 5% 0402")
      (fields (field (name "TOLERANCE") "5%") (field (name "VOLTAGE") "1/16W"))
      (libsource (lib "*") (part "RES"))
    )
    (comp (ref "R961")
      (value "0")
      (footprint "0402_CC")
      (description "RES MF ZERO OHM 1/16W 5% 0402")
      (fields (field (name "VOLTAGE") "1/16W") (field (name "TOLERANCE") "5%"))
      (libsource (lib "*") (part "RES"))
    )
    (comp (ref "R962")
      (value "0")
      (footprint "0402_CC")
      (description "RES MF ZERO OHM 1/16W 5% 0402")
      (fields (field (name "TOLERANCE") "5%") (field (name "VOLTAGE") "1/16W"))
      (libsource (lib "*") (part "RES"))
    )
    (comp (ref "R963")
      (value "0")
      (footprint "0402_CC")
      (description "RES MF ZERO OHM 1/16W 5% 0402")
      (fields (field (name "TOLERANCE") "5%") (field (name "VOLTAGE") "1/16W"))
      (libsource (lib "*") (part "RES"))
    )
    (comp (ref "R964")
      (value "0")
      (footprint "0402_CC")
      (description "RES MF ZERO OHM 1/16W 5% 0402")
      (fields (field (name "TOLERANCE") "5%") (field (name "VOLTAGE") "1/16W"))
      (libsource (lib "*") (part "RES"))
    )
    (comp (ref "R965")
      (value "0")
      (footprint "0402_CC")
      (description "RES MF ZERO OHM 1/16W 5% 0402")
      (fields (field (name "VOLTAGE") "1/16W") (field (name "TOLERANCE") "5%"))
      (libsource (lib "*") (part "RES"))
    )
    (comp (ref "R966")
      (value "0")
      (footprint "0402_CC")
      (description "RES MF ZERO OHM 1/16W 5% 0402")
      (fields (field (name "TOLERANCE") "5%") (field (name "VOLTAGE") "1/16W"))
      (libsource (lib "*") (part "RES"))
    )
    (comp (ref "R967")
      (value "0")
      (footprint "0402_CC")
      (description "RES MF ZERO OHM 1/16W 5% 0402")
      (fields (field (name "TOLERANCE") "5%") (field (name "VOLTAGE") "1/16W"))
      (libsource (lib "*") (part "RES"))
    )
    (comp (ref "R968")
      (value "0")
      (footprint "0402_CC")
      (description "RES MF ZERO OHM 1/16W 5% 0402")
      (fields (field (name "VOLTAGE") "1/16W") (field (name "TOLERANCE") "5%"))
      (libsource (lib "*") (part "RES"))
    )
    (comp (ref "R969")
      (value "0")
      (footprint "0402_CC")
      (description "RES MF ZERO OHM 1/16W 5% 0402")
      (fields (field (name "VOLTAGE") "1/16W") (field (name "TOLERANCE") "5%"))
      (libsource (lib "*") (part "RES"))
    )
    (comp (ref "R970")
      (value "0")
      (footprint "0402_CC")
      (description "RES MF ZERO OHM 1/16W 5% 0402")
      (fields (field (name "VOLTAGE") "1/16W") (field (name "TOLERANCE") "5%"))
      (libsource (lib "*") (part "RES"))
    )
    (comp (ref "R971")
      (value "10K")
      (footprint "0402_CC")
      (description "RES MF 10K 1/16W 5% 0402")
      (fields (field (name "ASSY_OPT") "DNP") (field (name "TOLERANCE") "5%"))
      (libsource (lib "*") (part "RES"))
    )
    (comp (ref "R972")
      (value "0")
      (footprint "0402_CC")
      (description "RES MF ZERO OHM 1/16W 5% 0402")
      (fields (field (name "VOLTAGE") "1/16W") (field (name "TOLERANCE") "5%"))
      (libsource (lib "*") (part "RES"))
    )
    (comp (ref "R973")
      (value "2.0")
      (footprint "RC0603_OV")
      (description "RES MF 2.0 OHM 1/8W 1% AEC-Q200 0603")
      (fields (field (name "TOLERANCE") "1%"))
      (libsource (lib "*") (part "RES"))
    )
    (comp (ref "R974")
      (value "0.05")
      (footprint "RC0805_OV")
      (description "RES MF 0.05OHM 1/4W 1% 0805")
      (fields (field (name "TOLERANCE") "1%"))
      (libsource (lib "*") (part "RES"))
    )
    (comp (ref "R975")
      (value "4.7K")
      (footprint "0402_CC")
      (description "RES MF 4.7K 1/10W 5% AEC-Q200 0402")
      (fields (field (name "TOLERANCE") "5%") (field (name "VOLTAGE") "50V"))
      (libsource (lib "*") (part "RES"))
    )
    (comp (ref "R976")
      (value "4.7K")
      (footprint "0402_CC")
      (description "RES MF 4.7K 1/10W 5% AEC-Q200 0402")
      (fields (field (name "TOLERANCE") "5%") (field (name "VOLTAGE") "50V"))
      (libsource (lib "*") (part "RES"))
    )
    (comp (ref "R977")
      (value "4.7K")
      (footprint "0402_CC")
      (description "RES MF 4.7K 1/10W 5% AEC-Q200 0402")
      (fields (field (name "TOLERANCE") "5%") (field (name "VOLTAGE") "50V"))
      (libsource (lib "*") (part "RES"))
    )
    (comp (ref "R978")
      (value "4.7K")
      (footprint "0402_CC")
      (description "RES MF 4.7K 1/10W 5% AEC-Q200 0402")
      (fields (field (name "TOLERANCE") "5%") (field (name "VOLTAGE") "50V"))
      (libsource (lib "*") (part "RES"))
    )
    (comp (ref "R979")
      (value "4.7K")
      (footprint "0402_CC")
      (description "RES MF 4.7K 1/10W 5% AEC-Q200 0402")
      (fields (field (name "TOLERANCE") "5%") (field (name "VOLTAGE") "50V"))
      (libsource (lib "*") (part "RES"))
    )
    (comp (ref "R980")
      (value "4.7K")
      (footprint "0402_CC")
      (description "RES MF 4.7K 1/10W 5% AEC-Q200 0402")
      (fields (field (name "TOLERANCE") "5%") (field (name "VOLTAGE") "50V"))
      (libsource (lib "*") (part "RES"))
    )
    (comp (ref "R981")
      (value "4.7K")
      (footprint "0402_CC")
      (description "RES MF 4.7K 1/10W 5% AEC-Q200 0402")
      (fields (field (name "TOLERANCE") "5%") (field (name "VOLTAGE") "50V"))
      (libsource (lib "*") (part "RES"))
    )
    (comp (ref "R982")
      (value "4.7K")
      (footprint "0402_CC")
      (description "RES MF 4.7K 1/10W 5% AEC-Q200 0402")
      (fields (field (name "TOLERANCE") "5%") (field (name "VOLTAGE") "50V"))
      (libsource (lib "*") (part "RES"))
    )
    (comp (ref "R983")
      (value "0")
      (footprint "0402_CC")
      (description "RES MF ZERO OHM 1/16W 5% 0402")
      (fields (field (name "TOLERANCE") "5%") (field (name "VOLTAGE") "1/16W"))
      (libsource (lib "*") (part "RES"))
    )
    (comp (ref "R984")
      (value "0")
      (footprint "0402_CC")
      (description "RES MF ZERO OHM 1/16W 5% 0402")
      (fields (field (name "TOLERANCE") "5%") (field (name "VOLTAGE") "1/16W"))
      (libsource (lib "*") (part "RES"))
    )
    (comp (ref "R985")
      (value "10K")
      (footprint "0402_CC")
      (description "RES MF 10K 1/16W 5% 0402")
      (fields (field (name "TOLERANCE") "5%"))
      (libsource (lib "*") (part "RES"))
    )
    (comp (ref "R987")
      (value "0")
      (footprint "0402_CC")
      (description "RES MF ZERO OHM 1/16W 5% 0402")
      (fields (field (name "TOLERANCE") "5%") (field (name "VOLTAGE") "1/16W"))
      (libsource (lib "*") (part "RES"))
    )
    (comp (ref "R988")
      (value "0")
      (footprint "0201_CC")
      (description "RES MF ZERO OHM 1/20W -- 0201")
      (libsource (lib "*") (part "RES"))
    )
    (comp (ref "R989")
      (value "0")
      (footprint "0402_CC")
      (description "RES MF ZERO OHM 1/16W 5% 0402")
      (fields (field (name "TOLERANCE") "5%") (field (name "VOLTAGE") "1/16W"))
      (libsource (lib "*") (part "RES"))
    )
    (comp (ref "R990")
      (value "0")
      (footprint "0201_CC")
      (description "RES MF ZERO OHM 1/20W -- 0201")
      (libsource (lib "*") (part "RES"))
    )
    (comp (ref "R991")
      (value "0")
      (footprint "0402_CC")
      (description "RES MF ZERO OHM 1/16W 5% 0402")
      (fields (field (name "TOLERANCE") "5%") (field (name "VOLTAGE") "1/16W"))
      (libsource (lib "*") (part "RES"))
    )
    (comp (ref "R992")
      (value "2.05K")
      (footprint "RC0402_25")
      (description "RES MF 2.05K  1/10W 1% AEC-Q200 0402")
      (fields (field (name "TOLERANCE") "1%") (field (name "VOLTAGE") "50V"))
      (libsource (lib "*") (part "RES"))
    )
    (comp (ref "R993")
      (value "10K")
      (footprint "0402_CC")
      (description "RES MF 10K 1/16W 5% 0402")
      (fields (field (name "TOLERANCE") "5%"))
      (libsource (lib "*") (part "RES"))
    )
    (comp (ref "R994")
      (value "10K")
      (footprint "0402_CC")
      (description "RES MF 10K 1/16W 5% 0402")
      (fields (field (name "ASSY_OPT") "DNP") (field (name "TOLERANCE") "5%"))
      (libsource (lib "*") (part "RES"))
    )
    (comp (ref "R995")
      (value "10K")
      (footprint "0402_CC")
      (description "RES MF 10K 1/16W 5% 0402")
      (fields (field (name "TOLERANCE") "5%"))
      (libsource (lib "*") (part "RES"))
    )
    (comp (ref "R996")
      (value "0")
      (footprint "0402_CC")
      (description "RES MF ZERO OHM 1/16W 5% 0402")
      (fields (field (name "TOLERANCE") "5%") (field (name "VOLTAGE") "1/16W"))
      (libsource (lib "*") (part "RES"))
    )
    (comp (ref "R997")
      (value "0")
      (footprint "0402_CC")
      (description "RES MF ZERO OHM 1/16W 5% 0402")
      (fields (field (name "TOLERANCE") "5%") (field (name "VOLTAGE") "1/16W"))
      (libsource (lib "*") (part "RES"))
    )
    (comp (ref "R998")
      (value "1.0")
      (footprint "RC0603_OV")
      (description "RES MF 1.00 OHM 1/10W 1% 0603")
      (fields (field (name "TOLERANCE") "1%"))
      (libsource (lib "*") (part "RES"))
    )
    (comp (ref "R999")
      (value "0.4")
      (footprint "RC0603_OV")
      (description "RES MF 0.4 OHM 1/10W 1% AEC-Q200 0603")
      (fields (field (name "TOLERANCE") "1%"))
      (libsource (lib "*") (part "RES"))
    )
    (comp (ref "R1000")
      (value "0")
      (footprint "0402_CC")
      (description "RES MF ZERO OHM 1/16W 5% 0402")
      (fields (field (name "TOLERANCE") "5%") (field (name "VOLTAGE") "1/16W"))
      (libsource (lib "*") (part "RES"))
    )
    (comp (ref "R1001")
      (value "0.25")
      (footprint "RC0805_OV")
      (description "RES 0.25 OHM 1% 1/8W 0805")
      (fields (field (name "TOLERANCE") "1%"))
      (libsource (lib "*") (part "RES"))
    )
    (comp (ref "R1002")
      (value "4.99")
      (footprint "RC0603_OV")
      (description "RES MF 4.99 OHM 0.1% 1/16W 0603")
      (fields (field (name "TOLERANCE") "0.1%"))
      (libsource (lib "*") (part "RES"))
    )
    (comp (ref "R1003")
      (value "0.1")
      (footprint "RC0805_OV")
      (description "RES MF 0.1 OHM 1/4W 1% AEC-Q200 0805")
      (fields (field (name "TOLERANCE") "1%"))
      (libsource (lib "*") (part "RES"))
    )
    (comp (ref "R1004")
      (value "0.1")
      (footprint "RC0805_OV")
      (description "RES MF 0.1 OHM 1/4W 1% AEC-Q200 0805")
      (fields (field (name "TOLERANCE") "1%"))
      (libsource (lib "*") (part "RES"))
    )
    (comp (ref "R1005")
      (value "0")
      (footprint "0402_CC")
      (description "RES MF ZERO OHM 1/16W 5% 0402")
      (fields (field (name "TOLERANCE") "5%") (field (name "VOLTAGE") "1/16W"))
      (libsource (lib "*") (part "RES"))
    )
    (comp (ref "R1006")
      (value "0")
      (footprint "0402_CC")
      (description "RES MF ZERO OHM 1/16W 5% 0402")
      (fields (field (name "TOLERANCE") "5%") (field (name "VOLTAGE") "1/16W"))
      (libsource (lib "*") (part "RES"))
    )
    (comp (ref "R1007")
      (value "0.25")
      (footprint "RC0805_OV")
      (description "RES 0.25 OHM 1% 1/8W 0805")
      (fields (field (name "TOLERANCE") "1%"))
      (libsource (lib "*") (part "RES"))
    )
    (comp (ref "R1008")
      (value "0")
      (footprint "0402_CC")
      (description "RES MF ZERO OHM 1/16W 5% 0402")
      (fields (field (name "TOLERANCE") "5%") (field (name "VOLTAGE") "1/16W"))
      (libsource (lib "*") (part "RES"))
    )
    (comp (ref "R1009")
      (value "100K")
      (footprint "0402_CC")
      (description "RES MF 100K 1/16W 5% 0402")
      (fields (field (name "VOLTAGE") "50V") (field (name "TOLERANCE") "5%"))
      (libsource (lib "*") (part "RES"))
    )
    (comp (ref "R1010")
      (value "2.2K")
      (footprint "RC0402_25")
      (description "RES MF 2.2K 1/16W 5% 0402")
      (fields (field (name "TOLERANCE") "5%"))
      (libsource (lib "*") (part "RES"))
    )
    (comp (ref "R1011")
      (value "10K")
      (footprint "0402_CC")
      (description "RES MF 10K 1/16W 5% 0402")
      (fields (field (name "TOLERANCE") "5%"))
      (libsource (lib "*") (part "RES"))
    )
    (comp (ref "R1012")
      (value "10K")
      (footprint "0402_CC")
      (description "RES MF 10K 1/16W 5% 0402")
      (fields (field (name "TOLERANCE") "5%"))
      (libsource (lib "*") (part "RES"))
    )
    (comp (ref "R1013")
      (value "10K")
      (footprint "0402_CC")
      (description "RES MF 10K 1/16W 5% 0402")
      (fields (field (name "TOLERANCE") "5%"))
      (libsource (lib "*") (part "RES"))
    )
    (comp (ref "R1014")
      (value "0.25")
      (footprint "RC0805_OV")
      (description "RES 0.25 OHM 1% 1/8W 0805")
      (fields (field (name "TOLERANCE") "1%"))
      (libsource (lib "*") (part "RES"))
    )
    (comp (ref "R1015")
      (value "0")
      (footprint "0402_CC")
      (description "RES MF ZERO OHM 1/16W 5% 0402")
      (fields (field (name "TOLERANCE") "5%") (field (name "VOLTAGE") "1/16W"))
      (libsource (lib "*") (part "RES"))
    )
    (comp (ref "R1016")
      (value "0")
      (footprint "0402_CC")
      (description "RES MF ZERO OHM 1/16W 5% 0402")
      (fields (field (name "VOLTAGE") "1/16W") (field (name "TOLERANCE") "5%"))
      (libsource (lib "*") (part "RES"))
    )
    (comp (ref "R1017")
      (value "0.1")
      (footprint "RC0805_OV")
      (description "RES MF 0.1 OHM 1/4W 1% AEC-Q200 0805")
      (fields (field (name "TOLERANCE") "1%"))
      (libsource (lib "*") (part "RES"))
    )
    (comp (ref "R1018")
      (value "0")
      (footprint "0402_CC")
      (description "RES MF ZERO OHM 1/16W 5% 0402")
      (fields (field (name "TOLERANCE") "5%") (field (name "VOLTAGE") "1/16W"))
      (libsource (lib "*") (part "RES"))
    )
    (comp (ref "R1019")
      (value "0")
      (footprint "0201_CC")
      (description "RES MF ZERO OHM 1/20W -- 0201")
      (libsource (lib "*") (part "RES"))
    )
    (comp (ref "R1020")
      (value "0")
      (footprint "0402_CC")
      (description "RES MF ZERO OHM 1/16W 5% 0402")
      (fields (field (name "TOLERANCE") "5%") (field (name "VOLTAGE") "1/16W"))
      (libsource (lib "*") (part "RES"))
    )
    (comp (ref "R1021")
      (value "0")
      (footprint "0201_CC")
      (description "RES MF ZERO OHM 1/20W -- 0201")
      (libsource (lib "*") (part "RES"))
    )
    (comp (ref "R1022")
      (value "0")
      (footprint "0402_CC")
      (description "RES MF ZERO OHM 1/16W 5% 0402")
      (fields (field (name "TOLERANCE") "5%") (field (name "VOLTAGE") "1/16W"))
      (libsource (lib "*") (part "RES"))
    )
    (comp (ref "R1023")
      (value "3.24K")
      (footprint "RC0402_25")
      (description "RES MF 3.24K 1/16W 1% 0402")
      (fields (field (name "TOLERANCE") "1%"))
      (libsource (lib "*") (part "RES"))
    )
    (comp (ref "R1024")
      (value "10K")
      (footprint "0402_CC")
      (description "RES MF 10K 1/16W 5% 0402")
      (fields (field (name "TOLERANCE") "5%"))
      (libsource (lib "*") (part "RES"))
    )
    (comp (ref "R1025")
      (value "10K")
      (footprint "0402_CC")
      (description "RES MF 10K 1/16W 5% 0402")
      (fields (field (name "ASSY_OPT") "DNP") (field (name "TOLERANCE") "5%"))
      (libsource (lib "*") (part "RES"))
    )
    (comp (ref "R1026")
      (value "0")
      (footprint "0402_CC")
      (description "RES MF ZERO OHM 1/16W 5% 0402")
      (fields (field (name "TOLERANCE") "5%") (field (name "VOLTAGE") "1/16W"))
      (libsource (lib "*") (part "RES"))
    )
    (comp (ref "R1027")
      (value "10K")
      (footprint "0402_CC")
      (description "RES MF 10K 1/16W 5% 0402")
      (fields (field (name "TOLERANCE") "5%"))
      (libsource (lib "*") (part "RES"))
    )
    (comp (ref "R1028")
      (value "0")
      (footprint "0402_CC")
      (description "RES MF ZERO OHM 1/16W 5% 0402")
      (fields (field (name "TOLERANCE") "5%") (field (name "VOLTAGE") "1/16W"))
      (libsource (lib "*") (part "RES"))
    )
    (comp (ref "R1029")
      (value "0")
      (footprint "0402_CC")
      (description "RES MF ZERO OHM 1/16W 5% 0402")
      (fields (field (name "TOLERANCE") "5%") (field (name "VOLTAGE") "1/16W"))
      (libsource (lib "*") (part "RES"))
    )
    (comp (ref "R1031")
      (value "0.1")
      (footprint "RC0805_OV")
      (description "RES MF 0.1 OHM 1/4W 1% AEC-Q200 0805")
      (fields (field (name "TOLERANCE") "1%"))
      (libsource (lib "*") (part "RES"))
    )
    (comp (ref "R1032")
      (value "0")
      (footprint "0402_CC")
      (description "RES MF ZERO OHM 1/16W 5% 0402")
      (fields (field (name "TOLERANCE") "5%") (field (name "VOLTAGE") "1/16W"))
      (libsource (lib "*") (part "RES"))
    )
    (comp (ref "R1033")
      (value "0")
      (footprint "0402_CC")
      (description "RES MF ZERO OHM 1/16W 5% 0402")
      (fields (field (name "TOLERANCE") "5%") (field (name "VOLTAGE") "1/16W"))
      (libsource (lib "*") (part "RES"))
    )
    (comp (ref "R1034")
      (value "0")
      (footprint "0402_CC")
      (description "RES MF ZERO OHM 1/16W 5% 0402")
      (fields (field (name "VOLTAGE") "1/16W") (field (name "TOLERANCE") "5%"))
      (libsource (lib "*") (part "RES"))
    )
    (comp (ref "R1035")
      (value "0")
      (footprint "0402_CC")
      (description "RES MF ZERO OHM 1/16W 5% 0402")
      (fields (field (name "VOLTAGE") "1/16W") (field (name "TOLERANCE") "5%"))
      (libsource (lib "*") (part "RES"))
    )
    (comp (ref "R1036")
      (value "4.7K")
      (footprint "0402_CC")
      (description "RES MF 4.7K 1/10W 5% AEC-Q200 0402")
      (fields (field (name "TOLERANCE") "5%") (field (name "VOLTAGE") "50V"))
      (libsource (lib "*") (part "RES"))
    )
    (comp (ref "R1037")
      (value "4.7K")
      (footprint "0402_CC")
      (description "RES MF 4.7K 1/10W 5% AEC-Q200 0402")
      (fields (field (name "TOLERANCE") "5%") (field (name "VOLTAGE") "50V"))
      (libsource (lib "*") (part "RES"))
    )
    (comp (ref "R1040")
      (value "0.02")
      (footprint "RC0805_OV")
      (description "RES MF 0.02OHM 1/4W 0.5% 0805")
      (fields (field (name "TOLERANCE") "0.5%"))
      (libsource (lib "*") (part "RES"))
    )
    (comp (ref "R1041")
      (value "0.02")
      (footprint "RC0805_OV")
      (description "RES MF 0.02OHM 1/4W 0.5% 0805")
      (fields (field (name "TOLERANCE") "0.5%"))
      (libsource (lib "*") (part "RES"))
    )
    (comp (ref "R1042")
      (value "0")
      (footprint "0402_CC")
      (description "RES MF ZERO OHM 1/16W 5% 0402")
      (fields (field (name "VOLTAGE") "1/16W") (field (name "TOLERANCE") "5%"))
      (libsource (lib "*") (part "RES"))
    )
    (comp (ref "R1043")
      (value "0")
      (footprint "0402_CC")
      (description "RES MF ZERO OHM 1/16W 5% 0402")
      (fields (field (name "TOLERANCE") "5%") (field (name "VOLTAGE") "1/16W"))
      (libsource (lib "*") (part "RES"))
    )
    (comp (ref "R1044")
      (value "0")
      (footprint "0402_CC")
      (description "RES MF ZERO OHM 1/16W 5% 0402")
      (fields (field (name "VOLTAGE") "1/16W") (field (name "TOLERANCE") "5%"))
      (libsource (lib "*") (part "RES"))
    )
    (comp (ref "R1045")
      (value "0")
      (footprint "0402_CC")
      (description "RES MF ZERO OHM 1/16W 5% 0402")
      (fields (field (name "TOLERANCE") "5%") (field (name "VOLTAGE") "1/16W"))
      (libsource (lib "*") (part "RES"))
    )
    (comp (ref "TP901")
      (value "TP_35MIL")
      (footprint "testpoint_35mil")
      (description "TEST POINT PAD .035 SMT, no part to order")
      (libsource (lib "*") (part "T POINT R"))
    )
    (comp (ref "TP902")
      (value "TP_35MIL")
      (footprint "testpoint_35mil")
      (description "TEST POINT PAD .035 SMT, no part to order")
      (libsource (lib "*") (part "T POINT R"))
    )
    (comp (ref "TP903")
      (value "TP_35MIL")
      (footprint "testpoint_35mil")
      (description "TEST POINT PAD .035 SMT, no part to order")
      (libsource (lib "*") (part "T POINT R"))
    )
    (comp (ref "TP904")
      (value "TP_35MIL")
      (footprint "testpoint_35mil")
      (description "TEST POINT PAD .035 SMT, no part to order")
      (libsource (lib "*") (part "T POINT R"))
    )
    (comp (ref "TP905")
      (value "TP_35MIL")
      (footprint "testpoint_35mil")
      (description "TEST POINT PAD .035 SMT, no part to order")
      (libsource (lib "*") (part "T POINT R"))
    )
    (comp (ref "TP906")
      (value "TP_35MIL")
      (footprint "testpoint_35mil")
      (description "TEST POINT PAD .035 SMT, no part to order")
      (libsource (lib "*") (part "T POINT R"))
    )
    (comp (ref "TP907")
      (value "TP_35MIL")
      (footprint "testpoint_35mil")
      (description "TEST POINT PAD .035 SMT, no part to order")
      (libsource (lib "*") (part "T POINT R"))
    )
    (comp (ref "TP908")
      (value "TP_35MIL")
      (footprint "testpoint_35mil")
      (description "TEST POINT PAD .035 SMT, no part to order")
      (libsource (lib "*") (part "T POINT R"))
    )
    (comp (ref "TP909")
      (value "TP_35MIL")
      (footprint "testpoint_35mil")
      (description "TEST POINT PAD .035 SMT, no part to order")
      (libsource (lib "*") (part "T POINT R"))
    )
    (comp (ref "TP910")
      (value "TP_35MIL")
      (footprint "testpoint_35mil")
      (description "TEST POINT PAD .035 SMT, no part to order")
      (libsource (lib "*") (part "T POINT R"))
    )
    (comp (ref "TP911")
      (value "TP_35MIL")
      (footprint "testpoint_35mil")
      (description "TEST POINT PAD .035 SMT, no part to order")
      (libsource (lib "*") (part "T POINT R"))
    )
    (comp (ref "TP917")
      (value "TP_35MIL")
      (footprint "testpoint_35mil")
      (description "TEST POINT PAD .035 SMT, no part to order")
      (libsource (lib "*") (part "T POINT R"))
    )
    (comp (ref "TP918")
      (value "TP_35MIL")
      (footprint "testpoint_35mil")
      (description "TEST POINT PAD .035 SMT, no part to order")
      (libsource (lib "*") (part "T POINT R"))
    )
    (comp (ref "TP919")
      (value "TP_35MIL")
      (footprint "testpoint_35mil")
      (description "TEST POINT PAD .035 SMT, no part to order")
      (libsource (lib "*") (part "T POINT R"))
    )
    (comp (ref "TP920")
      (value "TP_35MIL")
      (footprint "testpoint_35mil")
      (description "TEST POINT PAD .035 SMT, no part to order")
      (libsource (lib "*") (part "T POINT R"))
    )
    (comp (ref "TP921")
      (value "TP_35MIL")
      (footprint "testpoint_35mil")
      (description "TEST POINT PAD .035 SMT, no part to order")
      (libsource (lib "*") (part "T POINT R"))
    )
    (comp (ref "TP922")
      (value "TP_35MIL")
      (footprint "testpoint_35mil")
      (description "TEST POINT PAD .035 SMT, no part to order")
      (libsource (lib "*") (part "T POINT R"))
    )
    (comp (ref "TP923")
      (value "TP_35MIL")
      (footprint "testpoint_35mil")
      (description "TEST POINT PAD .035 SMT, no part to order")
      (libsource (lib "*") (part "T POINT R"))
    )
    (comp (ref "TP924")
      (value "TP_35MIL")
      (footprint "testpoint_35mil")
      (description "TEST POINT PAD .035 SMT, no part to order")
      (libsource (lib "*") (part "T POINT R"))
    )
    (comp (ref "TP925")
      (value "TP_35MIL")
      (footprint "testpoint_35mil")
      (description "TEST POINT PAD .035 SMT, no part to order")
      (libsource (lib "*") (part "T POINT R"))
    )
    (comp (ref "TP926")
      (value "TP_35MIL")
      (footprint "testpoint_35mil")
      (description "TEST POINT PAD .035 SMT, no part to order")
      (libsource (lib "*") (part "T POINT R"))
    )
    (comp (ref "TP927")
      (value "TP_35MIL")
      (footprint "testpoint_35mil")
      (description "TEST POINT PAD .035 SMT, no part to order")
      (libsource (lib "*") (part "T POINT R"))
    )
    (comp (ref "TP928")
      (value "TP_35MIL")
      (footprint "testpoint_35mil")
      (description "TEST POINT PAD .035 SMT, no part to order")
      (libsource (lib "*") (part "T POINT R"))
    )
    (comp (ref "TP929")
      (value "TP_35MIL")
      (footprint "testpoint_35mil")
      (description "TEST POINT PAD .035 SMT, no part to order")
      (libsource (lib "*") (part "T POINT R"))
    )
    (comp (ref "TP930")
      (value "TP_35MIL")
      (footprint "testpoint_35mil")
      (description "TEST POINT PAD .035 SMT, no part to order")
      (libsource (lib "*") (part "T POINT R"))
    )
    (comp (ref "TP931")
      (value "TP_35MIL")
      (footprint "testpoint_35mil")
      (description "TEST POINT PAD .035 SMT, no part to order")
      (libsource (lib "*") (part "T POINT R"))
    )
    (comp (ref "TP932")
      (value "TP_35MIL")
      (footprint "testpoint_35mil")
      (description "TEST POINT PAD .035 SMT, no part to order")
      (libsource (lib "*") (part "T POINT R"))
    )
    (comp (ref "TP933")
      (value "TP_35MIL")
      (footprint "testpoint_35mil")
      (description "TEST POINT PAD .035 SMT, no part to order")
      (libsource (lib "*") (part "T POINT R"))
    )
    (comp (ref "TP934")
      (value "TP_35MIL")
      (footprint "testpoint_35mil")
      (description "TEST POINT PAD .035 SMT, no part to order")
      (libsource (lib "*") (part "T POINT R"))
    )
    (comp (ref "TP935")
      (value "TP_35MIL")
      (footprint "testpoint_35mil")
      (description "TEST POINT PAD .035 SMT, no part to order")
      (libsource (lib "*") (part "T POINT R"))
    )
    (comp (ref "TP936")
      (value "TP_35MIL")
      (footprint "testpoint_35mil")
      (description "TEST POINT PAD .035 SMT, no part to order")
      (libsource (lib "*") (part "T POINT R"))
    )
    (comp (ref "TP937")
      (value "TP_35MIL")
      (footprint "testpoint_35mil")
      (description "TEST POINT PAD .035 SMT, no part to order")
      (libsource (lib "*") (part "T POINT R"))
    )
    (comp (ref "TP938")
      (value "TP_35MIL")
      (footprint "testpoint_35mil")
      (description "TEST POINT PAD .035 SMT, no part to order")
      (libsource (lib "*") (part "T POINT R"))
    )
    (comp (ref "TP939")
      (value "TP_35MIL")
      (footprint "testpoint_35mil")
      (description "TEST POINT PAD .035 SMT, no part to order")
      (libsource (lib "*") (part "T POINT R"))
    )
    (comp (ref "TP940")
      (value "TP_35MIL")
      (footprint "testpoint_35mil")
      (description "TEST POINT PAD .035 SMT, no part to order")
      (libsource (lib "*") (part "T POINT R"))
    )
    (comp (ref "TP941")
      (value "TP_35MIL")
      (footprint "testpoint_35mil")
      (description "TEST POINT PAD .035 SMT, no part to order")
      (libsource (lib "*") (part "T POINT R"))
    )
    (comp (ref "TP942")
      (value "TP_35MIL")
      (footprint "testpoint_35mil")
      (description "TEST POINT PAD .035 SMT, no part to order")
      (libsource (lib "*") (part "T POINT R"))
    )
    (comp (ref "TP943")
      (value "TP_35MIL")
      (footprint "testpoint_35mil")
      (description "TEST POINT PAD .035 SMT, no part to order")
      (libsource (lib "*") (part "T POINT R"))
    )
    (comp (ref "TP944")
      (value "TP_35MIL")
      (footprint "testpoint_35mil")
      (description "TEST POINT PAD .035 SMT, no part to order")
      (libsource (lib "*") (part "T POINT R"))
    )
    (comp (ref "TP945")
      (value "TP_35MIL")
      (footprint "testpoint_35mil")
      (description "TEST POINT PAD .035 SMT, no part to order")
      (libsource (lib "*") (part "T POINT R"))
    )
    (comp (ref "TP946")
      (value "TP_35MIL")
      (footprint "testpoint_35mil")
      (description "TEST POINT PAD .035 SMT, no part to order")
      (libsource (lib "*") (part "T POINT R"))
    )
    (comp (ref "TP947")
      (value "TP_35MIL")
      (footprint "testpoint_35mil")
      (description "TEST POINT PAD .035 SMT, no part to order")
      (libsource (lib "*") (part "T POINT R"))
    )
    (comp (ref "TP948")
      (value "TP_35MIL")
      (footprint "testpoint_35mil")
      (description "TEST POINT PAD .035 SMT, no part to order")
      (libsource (lib "*") (part "T POINT R"))
    )
    (comp (ref "TP949")
      (value "TP_35MIL")
      (footprint "testpoint_35mil")
      (description "TEST POINT PAD .035 SMT, no part to order")
      (libsource (lib "*") (part "T POINT R"))
    )
    (comp (ref "TP950")
      (value "TP_35MIL")
      (footprint "testpoint_35mil")
      (description "TEST POINT PAD .035 SMT, no part to order")
      (libsource (lib "*") (part "T POINT R"))
    )
    (comp (ref "TP951")
      (value "TP_35MIL")
      (footprint "testpoint_35mil")
      (description "TEST POINT PAD .035 SMT, no part to order")
      (libsource (lib "*") (part "T POINT R"))
    )
    (comp (ref "TP952")
      (value "TP_35MIL")
      (footprint "testpoint_35mil")
      (description "TEST POINT PAD .035 SMT, no part to order")
      (libsource (lib "*") (part "T POINT R"))
    )
    (comp (ref "TP953")
      (value "TP_35MIL")
      (footprint "testpoint_35mil")
      (description "TEST POINT PAD .035 SMT, no part to order")
      (libsource (lib "*") (part "T POINT R"))
    )
    (comp (ref "TP954")
      (value "TP_35MIL")
      (footprint "testpoint_35mil")
      (description "TEST POINT PAD .035 SMT, no part to order")
      (libsource (lib "*") (part "T POINT R"))
    )
    (comp (ref "TP955")
      (value "TP_35MIL")
      (footprint "testpoint_35mil")
      (description "TEST POINT PAD .035 SMT, no part to order")
      (libsource (lib "*") (part "T POINT R"))
    )
    (comp (ref "TP956")
      (value "TP_35MIL")
      (footprint "testpoint_35mil")
      (description "TEST POINT PAD .035 SMT, no part to order")
      (libsource (lib "*") (part "T POINT R"))
    )
    (comp (ref "TP957")
      (value "TP_35MIL")
      (footprint "testpoint_35mil")
      (description "TEST POINT PAD .035 SMT, no part to order")
      (libsource (lib "*") (part "T POINT R"))
    )
    (comp (ref "TP958")
      (value "TP_35MIL")
      (footprint "testpoint_35mil")
      (description "TEST POINT PAD .035 SMT, no part to order")
      (libsource (lib "*") (part "T POINT R"))
    )
    (comp (ref "TP959")
      (value "TP_35MIL")
      (footprint "testpoint_35mil")
      (description "TEST POINT PAD .035 SMT, no part to order")
      (libsource (lib "*") (part "T POINT R"))
    )
    (comp (ref "TP960")
      (value "TP_35MIL")
      (footprint "testpoint_35mil")
      (description "TEST POINT PAD .035 SMT, no part to order")
      (libsource (lib "*") (part "T POINT R"))
    )
    (comp (ref "TP961")
      (value "TP_35MIL")
      (footprint "testpoint_35mil")
      (description "TEST POINT PAD .035 SMT, no part to order")
      (libsource (lib "*") (part "T POINT R"))
    )
    (comp (ref "TP962")
      (value "TP_35MIL")
      (footprint "testpoint_35mil")
      (description "TEST POINT PAD .035 SMT, no part to order")
      (libsource (lib "*") (part "T POINT R"))
    )
    (comp (ref "TP963")
      (value "TP_35MIL")
      (footprint "testpoint_35mil")
      (description "TEST POINT PAD .035 SMT, no part to order")
      (libsource (lib "*") (part "T POINT R"))
    )
    (comp (ref "TP964")
      (value "TP_35MIL")
      (footprint "testpoint_35mil")
      (description "TEST POINT PAD .035 SMT, no part to order")
      (libsource (lib "*") (part "T POINT R"))
    )
    (comp (ref "TP965")
      (value "TP_35MIL")
      (footprint "testpoint_35mil")
      (description "TEST POINT PAD .035 SMT, no part to order")
      (libsource (lib "*") (part "T POINT R"))
    )
    (comp (ref "U901")
      (value "DML3006LFDS-7")
      (footprint "dfn2020_0p5_sq2")
      (description "IC LOAD SW 0.5-13.5V 10.5A 3-5.5V DFN2020-8")
      (fields (field (name "VOLTAGE") "3-5.5V"))
      (libsource (lib "*") (part "DML3006LFDS-7_A_0"))
    )
    (comp (ref "U902")
      (value "PAC1934T-I/JQ")
      (footprint "qfn16_0p65_4X4_a")
      (description "IC MULTI CHANNEL POWER/ENERGY MONITOR  2.7-5.5V UQFN16")
      (libsource (lib "*") (part "PAC1934_UQFN16_A"))
    )
    (comp (ref "U903")
      (value "TPS22990N")
      (footprint "wson10_0p5_2p1x3p1")
      (description "IC LOAD SWITCH 10A 2.5-5.5V WSON10")
      (fields (field (name "VOLTAGE") "2.5-5.5V"))
      (libsource (lib "*") (part "TPS22990NDMLT_WSON10_2"))
    )
    (comp (ref "U904")
      (value "PAC1934T-I/JQ")
      (footprint "qfn16_0p65_4X4_a")
      (description "IC MULTI CHANNEL POWER/ENERGY MONITOR  2.7-5.5V UQFN16")
      (libsource (lib "*") (part "PAC1934_UQFN16_A"))
    )
    (comp (ref "U905")
      (value "RT9193")
      (footprint "sot23-5")
      (description "IC VREG LDO 3.3V 300MA SOT-23-5")
      (libsource (lib "*") (part "RT9193-33PB"))
    )
    (comp (ref "U906")
      (value "TPS22990N")
      (footprint "wson10_0p5_2p1x3p1")
      (description "IC LOAD SWITCH 10A 2.5-5.5V WSON10")
      (fields (field (name "VOLTAGE") "2.5-5.5V"))
      (libsource (lib "*") (part "TPS22990NDMLT_WSON10_2"))
    )
    (comp (ref "U907")
      (value "PAC1934T-I/JQ")
      (footprint "qfn16_0p65_4X4_a")
      (description "IC MULTI CHANNEL POWER/ENERGY MONITOR  2.7-5.5V UQFN16")
      (libsource (lib "*") (part "PAC1934_UQFN16_A"))
    )
    (comp (ref "U908")
      (value "TPS22990N")
      (footprint "wson10_0p5_2p1x3p1")
      (description "IC LOAD SWITCH 10A 2.5-5.5V WSON10")
      (fields (field (name "VOLTAGE") "2.5-5.5V"))
      (libsource (lib "*") (part "TPS22990NDMLT_WSON10_2"))
    )
    (comp (ref "U909")
      (value "ADP5585ACPZ-00-R7")
      (footprint "lfcsp_16_0p5_3x3_a")
      (description "IC I/O EXPANDER I2C 1.65-3.6V LFCSP16")
      (libsource (lib "*") (part "ADP5585ACPZ_LFCSP16_A"))
    )
    (comp (ref "U910")
      (value "TPS22990N")
      (footprint "wson10_0p5_2p1x3p1")
      (description "IC LOAD SWITCH 10A 2.5-5.5V WSON10")
      (fields (field (name "VOLTAGE") "2.5-5.5V"))
      (libsource (lib "*") (part "TPS22990NDMLT_WSON10_2"))
    )
    (comp (ref "U911")
      (value "PAC1934T-I/JQ")
      (footprint "qfn16_0p65_4X4_a")
      (description "IC MULTI CHANNEL POWER/ENERGY MONITOR  2.7-5.5V UQFN16")
      (libsource (lib "*") (part "PAC1934_UQFN16_A"))
    )
    (comp (ref "U912")
      (value "PAC1934T-I/JQ")
      (footprint "qfn16_0p65_4X4_a")
      (description "IC MULTI CHANNEL POWER/ENERGY MONITOR  2.7-5.5V UQFN16")
      (libsource (lib "*") (part "PAC1934_UQFN16_A"))
    )
    (comp (ref "U913")
      (value "PCT2075")
      (footprint "hwson8_0p5_3p1x2p1")
      (description "IC I2C DIGITAL TEMP SENSOR AND THERMAL WDG 2.7-5.5V HWSON8")
      (fields (field (name "VOLTAGE") "2.7-5.5V"))
      (libsource (lib "*") (part "PCT2075 _SON8_EP"))
    )
    (comp (ref "U914")
      (value "93LC56BT")
      (footprint "sot23-6")
      (description "IC MEM EEPROM SERIAL 2K 16BIT 2.5-5.5V SOT23-6")
      (fields (field (name "VOLTAGE") "2.5-5.5V"))
      (libsource (lib "*") (part "93AA56BT_SOT23-6"))
    )
  )
  (nets
    (net (code "1") (name "/FSC_CTRL_H1") (class "Default")
      (node (ref "R969") (pin "2") (pinfunction "2_2") (pintype "passive"))
      (node (ref "TP909") (pin "1") (pinfunction "TP_1") (pintype "passive"))
      (node (ref "U901") (pin "2") (pinfunction "EN_2") (pintype "input"))
    )
    (net (code "2") (name "/FSC_CTRL_H2") (class "Default")
      (node (ref "R970") (pin "2") (pinfunction "2_2") (pintype "passive"))
      (node (ref "TP910") (pin "1") (pinfunction "TP_1") (pintype "passive"))
      (node (ref "U903") (pin "5") (pinfunction "ON_5") (pintype "input"))
    )
    (net (code "3") (name "/FSC_CTRL_H3") (class "Default")
      (node (ref "R972") (pin "2") (pinfunction "2_2") (pintype "passive"))
      (node (ref "TP911") (pin "1") (pinfunction "TP_1") (pintype "passive"))
      (node (ref "U906") (pin "5") (pinfunction "ON_5") (pintype "input"))
    )
    (net (code "4") (name "/FSC_CTRL_H4") (class "Default")
      (node (ref "R1034") (pin "2") (pinfunction "2_2") (pintype "passive"))
      (node (ref "TP917") (pin "1") (pinfunction "TP_1") (pintype "passive"))
      (node (ref "U908") (pin "5") (pinfunction "ON_5") (pintype "input"))
    )
    (net (code "5") (name "/FSC_CTRL_H5") (class "Default")
      (node (ref "R1035") (pin "2") (pinfunction "2_2") (pintype "passive"))
      (node (ref "TP918") (pin "1") (pinfunction "TP_1") (pintype "passive"))
      (node (ref "U910") (pin "5") (pinfunction "ON_5") (pintype "input"))
    )
    (net (code "6") (name "/FSC_CTRL_L1") (class "Default")
      (node (ref "R960") (pin "2") (pinfunction "2_2") (pintype "passive"))
      (node (ref "TP961") (pin "1") (pinfunction "TP_1") (pintype "passive"))
    )
    (net (code "7") (name "/FSC_CTRL_L2") (class "Default")
      (node (ref "R962") (pin "2") (pinfunction "2_2") (pintype "passive"))
      (node (ref "TP962") (pin "1") (pinfunction "TP_1") (pintype "passive"))
    )
    (net (code "8") (name "/FSC_CTRL_L3") (class "Default")
      (node (ref "R963") (pin "2") (pinfunction "2_2") (pintype "passive"))
      (node (ref "TP963") (pin "1") (pinfunction "TP_1") (pintype "passive"))
    )
    (net (code "9") (name "/FSC_CTRL_L4") (class "Default")
      (node (ref "R964") (pin "2") (pinfunction "2_2") (pintype "passive"))
      (node (ref "TP964") (pin "1") (pinfunction "TP_1") (pintype "passive"))
    )
    (net (code "10") (name "/FSC_CTRL_L5") (class "Default")
      (node (ref "R966") (pin "2") (pinfunction "2_2") (pintype "passive"))
      (node (ref "TP965") (pin "1") (pinfunction "TP_1") (pintype "passive"))
    )
    (net (code "11") (name "/FT_EECLK") (class "Default")
      (node (ref "J901") (pin "7") (pinfunction "A4_7") (pintype "passive"))
      (node (ref "R1016") (pin "2") (pinfunction "2_2") (pintype "passive"))
    )
    (net (code "12") (name "/FT_EECS") (class "Default")
      (node (ref "J901") (pin "10") (pinfunction "B5_10") (pintype "passive"))
      (node (ref "R1018") (pin "2") (pinfunction "2_2") (pintype "passive"))
    )
    (net (code "13") (name "/FT_EEDATA") (class "Default")
      (node (ref "J901") (pin "9") (pinfunction "A5_9") (pintype "passive"))
      (node (ref "R1015") (pin "2") (pinfunction "2_2") (pintype "passive"))
    )
    (net (code "14") (name "/FT_IOEXP1_SCL") (class "Default")
      (node (ref "R968") (pin "2") (pinfunction "2_2") (pintype "passive"))
      (node (ref "U909") (pin "15") (pinfunction "SCL_15") (pintype "input"))
    )
    (net (code "15") (name "/FT_IOEXP1_SDA") (class "Default")
      (node (ref "R965") (pin "2") (pinfunction "2_2") (pintype "passive"))
      (node (ref "U909") (pin "14") (pinfunction "SDA_14") (pintype "bidirectional"))
    )
    (net (code "16") (name "/FT_IO_nINT") (class "Default")
      (node (ref "J901") (pin "4") (pinfunction "B2_4") (pintype "passive"))
      (node (ref "R961") (pin "1") (pinfunction "1_1") (pintype "passive"))
      (node (ref "TP906") (pin "1") (pinfunction "TP_1") (pintype "passive"))
    )
    (net (code "17") (name "/FT_IO_nRST") (class "Default")
      (node (ref "D903") (pin "C") (pinfunction "C_C") (pintype "passive"))
      (node (ref "J901") (pin "6") (pinfunction "B3_6") (pintype "passive"))
      (node (ref "TP907") (pin "1") (pinfunction "TP_1") (pintype "passive"))
    )
    (net (code "18") (name "/FT_SCL") (class "Default")
      (node (ref "J901") (pin "3") (pinfunction "A2_3") (pintype "passive"))
      (node (ref "R1019") (pin "2") (pinfunction "2_2") (pintype "passive"))
      (node (ref "R1033") (pin "1") (pinfunction "1_1") (pintype "passive"))
      (node (ref "R906") (pin "2") (pinfunction "2_2") (pintype "passive"))
      (node (ref "R926") (pin "2") (pinfunction "2_2") (pintype "passive"))
      (node (ref "R946") (pin "2") (pinfunction "2_2") (pintype "passive"))
      (node (ref "R968") (pin "1") (pinfunction "1_1") (pintype "passive"))
      (node (ref "R988") (pin "2") (pinfunction "2_2") (pintype "passive"))
      (node (ref "TP904") (pin "1") (pinfunction "TP_1") (pintype "passive"))
    )
    (net (code "19") (name "/FT_SDA") (class "Default")
      (node (ref "J901") (pin "5") (pinfunction "A3_5") (pintype "passive"))
      (node (ref "R1021") (pin "2") (pinfunction "2_2") (pintype "passive"))
      (node (ref "R1032") (pin "1") (pinfunction "1_1") (pintype "passive"))
      (node (ref "R910") (pin "2") (pinfunction "2_2") (pintype "passive"))
      (node (ref "R928") (pin "2") (pinfunction "2_2") (pintype "passive"))
      (node (ref "R948") (pin "2") (pinfunction "2_2") (pintype "passive"))
      (node (ref "R965") (pin "1") (pinfunction "1_1") (pintype "passive"))
      (node (ref "R990") (pin "2") (pinfunction "2_2") (pintype "passive"))
      (node (ref "TP905") (pin "1") (pinfunction "TP_1") (pintype "passive"))
    )
    (net (code "20") (name "/M1_SCL") (class "Default")
      (node (ref "R906") (pin "1") (pinfunction "1_1") (pintype "passive"))
      (node (ref "U902") (pin "4") (pinfunction "SM_CLK_4") (pintype "input"))
    )
    (net (code "21") (name "/M1_SDA") (class "Default")
      (node (ref "R910") (pin "1") (pinfunction "1_1") (pintype "passive"))
      (node (ref "U902") (pin "5") (pinfunction "SM_DATA_5") (pintype "bidirectional"))
    )
    (net (code "22") (name "/M2_SCL") (class "Default")
      (node (ref "R926") (pin "1") (pinfunction "1_1") (pintype "passive"))
      (node (ref "U904") (pin "4") (pinfunction "SM_CLK_4") (pintype "input"))
    )
    (net (code "23") (name "/M2_SDA") (class "Default")
      (node (ref "R928") (pin "1") (pinfunction "1_1") (pintype "passive"))
      (node (ref "U904") (pin "5") (pinfunction "SM_DATA_5") (pintype "bidirectional"))
    )
    (net (code "24") (name "/M3_SCL") (class "Default")
      (node (ref "R946") (pin "1") (pinfunction "1_1") (pintype "passive"))
      (node (ref "U907") (pin "4") (pinfunction "SM_CLK_4") (pintype "input"))
    )
    (net (code "25") (name "/M3_SDA") (class "Default")
      (node (ref "R948") (pin "1") (pinfunction "1_1") (pintype "passive"))
      (node (ref "U907") (pin "5") (pinfunction "SM_DATA_5") (pintype "bidirectional"))
    )
    (net (code "26") (name "/M4_SCL") (class "Default")
      (node (ref "R988") (pin "1") (pinfunction "1_1") (pintype "passive"))
      (node (ref "U911") (pin "4") (pinfunction "SM_CLK_4") (pintype "input"))
    )
    (net (code "27") (name "/M4_SDA") (class "Default")
      (node (ref "R990") (pin "1") (pinfunction "1_1") (pintype "passive"))
      (node (ref "U911") (pin "5") (pinfunction "SM_DATA_5") (pintype "bidirectional"))
    )
    (net (code "28") (name "/M5_SCL") (class "Default")
      (node (ref "R1019") (pin "1") (pinfunction "1_1") (pintype "passive"))
      (node (ref "U912") (pin "4") (pinfunction "SM_CLK_4") (pintype "input"))
    )
    (net (code "29") (name "/M5_SDA") (class "Default")
      (node (ref "R1021") (pin "1") (pinfunction "1_1") (pintype "passive"))
      (node (ref "U912") (pin "5") (pinfunction "SM_DATA_5") (pintype "bidirectional"))
    )
    (net (code "30") (name "/TEMP_nINT") (class "Default")
      (node (ref "R1009") (pin "2") (pinfunction "2_2") (pintype "passive"))
      (node (ref "TP908") (pin "1") (pinfunction "TP_1") (pintype "passive"))
      (node (ref "U913") (pin "3") (pinfunction "OS_3") (pintype "open_collector"))
    )
    (net (code "31") (name "BB_VSYS_5V") (class "Default")
      (node (ref "C918") (pin "1") (pinfunction "1_1") (pintype "passive"))
      (node (ref "R901") (pin "1") (pinfunction "1_1") (pintype "passive"))
      (node (ref "R911") (pin "1") (pinfunction "1_1") (pintype "passive"))
      (node (ref "TP901") (pin "1") (pinfunction "TP_1") (pintype "passive"))
      (node (ref "TP919") (pin "1") (pinfunction "TP_1") (pintype "passive"))
      (node (ref "U901") (pin "1") (pinfunction "VIN_1_1") (pintype "input"))
      (node (ref "U901") (pin "8") (pinfunction "VIN_2_8") (pintype "input"))
      (node (ref "U905") (pin "1") (pinfunction "VIN_1") (pintype "passive"))
      (node (ref "U905") (pin "3") (pinfunction "EN_3") (pintype "passive"))
    )
    (net (code "32") (name "GND") (class "Default")
      (node (ref "C901") (pin "2") (pinfunction "2_2") (pintype "passive"))
      (node (ref "C903") (pin "2") (pinfunction "2_2") (pintype "passive"))
      (node (ref "C904") (pin "2") (pinfunction "2_2") (pintype "passive"))
      (node (ref "C906") (pin "2") (pinfunction "2_2") (pintype "passive"))
      (node (ref "C909") (pin "2") (pinfunction "2_2") (pintype "passive"))
      (node (ref "C911") (pin "2") (pinfunction "2_2") (pintype "passive"))
      (node (ref "C912") (pin "2") (pinfunction "2_2") (pintype "passive"))
      (node (ref "C913") (pin "2") (pinfunction "2_2") (pintype "passive"))
      (node (ref "C914") (pin "2") (pinfunction "2_2") (pintype "passive"))
      (node (ref "C915") (pin "2") (pinfunction "2_2") (pintype "passive"))
      (node (ref "C916") (pin "2") (pinfunction "2_2") (pintype "passive"))
      (node (ref "C918") (pin "2") (pinfunction "2_2") (pintype "passive"))
      (node (ref "C919") (pin "2") (pinfunction "2_2") (pintype "passive"))
      (node (ref "C922") (pin "2") (pinfunction "2_2") (pintype "passive"))
      (node (ref "C923") (pin "2") (pinfunction "2_2") (pintype "passive"))
      (node (ref "C925") (pin "2") (pinfunction "2_2") (pintype "passive"))
      (node (ref "C926") (pin "2") (pinfunction "2_2") (pintype "passive"))
      (node (ref "C928") (pin "2") (pinfunction "2_2") (pintype "passive"))
      (node (ref "C929") (pin "2") (pinfunction "2_2") (pintype "passive"))
      (node (ref "C930") (pin "2") (pinfunction "2_2") (pintype "passive"))
      (node (ref "C931") (pin "2") (pinfunction "2_2") (pintype "passive"))
      (node (ref "C934") (pin "2") (pinfunction "2_2") (pintype "passive"))
      (node (ref "C935") (pin "2") (pinfunction "2_2") (pintype "passive"))
      (node (ref "C937") (pin "2") (pinfunction "2_2") (pintype "passive"))
      (node (ref "C938") (pin "2") (pinfunction "2_2") (pintype "passive"))
      (node (ref "C942") (pin "2") (pinfunction "2_2") (pintype "passive"))
      (node (ref "C943") (pin "2") (pinfunction "2_2") (pintype "passive"))
      (node (ref "C944") (pin "2") (pinfunction "2_2") (pintype "passive"))
      (node (ref "C946") (pin "2") (pinfunction "2_2") (pintype "passive"))
      (node (ref "C947") (pin "2") (pinfunction "2_2") (pintype "passive"))
      (node (ref "C951") (pin "2") (pinfunction "2_2") (pintype "passive"))
      (node (ref "C952") (pin "2") (pinfunction "2_2") (pintype "passive"))
      (node (ref "C953") (pin "2") (pinfunction "2_2") (pintype "passive"))
      (node (ref "C954") (pin "2") (pinfunction "2_2") (pintype "passive"))
      (node (ref "J901") (pin "12") (pinfunction "B6_12") (pintype "passive"))
      (node (ref "J901") (pin "2") (pinfunction "B1_2") (pintype "passive"))
      (node (ref "R1023") (pin "2") (pinfunction "2_2") (pintype "passive"))
      (node (ref "R1024") (pin "2") (pinfunction "2_2") (pintype "passive"))
      (node (ref "R912") (pin "2") (pinfunction "2_2") (pintype "passive"))
      (node (ref "R913") (pin "2") (pinfunction "2_2") (pintype "passive"))
      (node (ref "R930") (pin "2") (pinfunction "2_2") (pintype "passive"))
      (node (ref "R933") (pin "2") (pinfunction "2_2") (pintype "passive"))
      (node (ref "R950") (pin "2") (pinfunction "2_2") (pintype "passive"))
      (node (ref "R955") (pin "2") (pinfunction "2_2") (pintype "passive"))
      (node (ref "R978") (pin "2") (pinfunction "2_2") (pintype "passive"))
      (node (ref "R979") (pin "2") (pinfunction "2_2") (pintype "passive"))
      (node (ref "R980") (pin "2") (pinfunction "2_2") (pintype "passive"))
      (node (ref "R981") (pin "2") (pinfunction "2_2") (pintype "passive"))
      (node (ref "R982") (pin "2") (pinfunction "2_2") (pintype "passive"))
      (node (ref "R992") (pin "2") (pinfunction "2_2") (pintype "passive"))
      (node (ref "R993") (pin "2") (pinfunction "2_2") (pintype "passive"))
      (node (ref "U901") (pin "4") (pinfunction "GND_4") (pintype "power_in"))
      (node (ref "U902") (pin "17") (pinfunction "EP_17") (pintype "power_in"))
      (node (ref "U902") (pin "3") (pinfunction "GND_3") (pintype "power_in"))
      (node (ref "U903") (pin "6") (pinfunction "GND_6") (pintype "power_in"))
      (node (ref "U904") (pin "17") (pinfunction "EP_17") (pintype "power_in"))
      (node (ref "U904") (pin "3") (pinfunction "GND_3") (pintype "power_in"))
      (node (ref "U905") (pin "2") (pinfunction "GND_2") (pintype "passive"))
      (node (ref "U906") (pin "6") (pinfunction "GND_6") (pintype "power_in"))
      (node (ref "U907") (pin "17") (pinfunction "EP_17") (pintype "power_in"))
      (node (ref "U907") (pin "3") (pinfunction "GND_3") (pintype "power_in"))
      (node (ref "U908") (pin "6") (pinfunction "GND_6") (pintype "power_in"))
      (node (ref "U909") (pin "13") (pinfunction "GND_13") (pintype "power_in"))
      (node (ref "U909") (pin "17") (pinfunction "EPAD_17") (pintype "passive"))
      (node (ref "U910") (pin "6") (pinfunction "GND_6") (pintype "power_in"))
      (node (ref "U911") (pin "17") (pinfunction "EP_17") (pintype "power_in"))
      (node (ref "U911") (pin "3") (pinfunction "GND_3") (pintype "power_in"))
      (node (ref "U912") (pin "17") (pinfunction "EP_17") (pintype "power_in"))
      (node (ref "U912") (pin "3") (pinfunction "GND_3") (pintype "power_in"))
      (node (ref "U913") (pin "4") (pinfunction "GND_4") (pintype "power_in"))
      (node (ref "U913") (pin "5") (pinfunction "A2_5") (pintype "input"))
      (node (ref "U913") (pin "6") (pinfunction "A1_6") (pintype "input"))
      (node (ref "U913") (pin "7") (pinfunction "A0_7") (pintype "input"))
      (node (ref "U913") (pin "9") (pinfunction "EP_GND_9") (pintype "power_in"))
      (node (ref "U914") (pin "2") (pinfunction "VSS_2") (pintype "power_in"))
    )
    (net (code "33") (name "LPD4{slash}x_VDD1") (class "Default")
      (node (ref "R1006") (pin "1") (pinfunction "1_1") (pintype "passive"))
      (node (ref "R1014") (pin "2") (pinfunction "2_2") (pintype "passive"))
      (node (ref "TP947") (pin "1") (pinfunction "TP_1") (pintype "passive"))
    )
    (net (code "34") (name "LPD4{slash}x_VDD2") (class "Default")
      (node (ref "R1017") (pin "2") (pinfunction "2_2") (pintype "passive"))
      (node (ref "R1026") (pin "1") (pinfunction "1_1") (pintype "passive"))
      (node (ref "TP951") (pin "1") (pinfunction "TP_1") (pintype "passive"))
    )
    (net (code "35") (name "LPD4{slash}x_VDD2_1V1") (class "Default")
      (node (ref "R1017") (pin "1") (pinfunction "1_1") (pintype "passive"))
      (node (ref "R1022") (pin "1") (pinfunction "1_1") (pintype "passive"))
      (node (ref "R942") (pin "1") (pinfunction "1_1") (pintype "passive"))
      (node (ref "R949") (pin "1") (pinfunction "1_1") (pintype "passive"))
      (node (ref "TP928") (pin "1") (pinfunction "TP_1") (pintype "passive"))
      (node (ref "TP950") (pin "1") (pinfunction "TP_1") (pintype "passive"))
      (node (ref "U908") (pin "11") (pinfunction "VIN_2_11") (pintype "input"))
      (node (ref "U908") (pin "3") (pinfunction "VIN_1_3") (pintype "input"))
    )
    (net (code "36") (name "LPD4{slash}x_VDDQ") (class "Default")
      (node (ref "R1007") (pin "2") (pinfunction "2_2") (pintype "passive"))
      (node (ref "R923") (pin "1") (pinfunction "1_1") (pintype "passive"))
      (node (ref "TP949") (pin "1") (pinfunction "TP_1") (pintype "passive"))
    )
    (net (code "37") (name "LPD4{slash}x_VDDQ_0V6") (class "Default")
      (node (ref "R1007") (pin "1") (pinfunction "1_1") (pintype "passive"))
      (node (ref "R921") (pin "1") (pinfunction "1_1") (pintype "passive"))
      (node (ref "R941") (pin "1") (pinfunction "1_1") (pintype "passive"))
      (node (ref "R973") (pin "1") (pinfunction "1_1") (pintype "passive"))
      (node (ref "TP931") (pin "1") (pinfunction "TP_1") (pintype "passive"))
      (node (ref "TP948") (pin "1") (pinfunction "TP_1") (pintype "passive"))
      (node (ref "U910") (pin "11") (pinfunction "VIN_2_11") (pintype "input"))
      (node (ref "U910") (pin "3") (pinfunction "VIN_1_3") (pintype "input"))
    )
    (net (code "38") (name "NVCC_1P8") (class "Default")
      (node (ref "R1004") (pin "2") (pinfunction "2_2") (pintype "passive"))
      (node (ref "R1029") (pin "1") (pinfunction "1_1") (pintype "passive"))
      (node (ref "TP943") (pin "1") (pinfunction "TP_1") (pintype "passive"))
    )
    (net (code "39") (name "NVCC_3P3") (class "Default")
      (node (ref "R1003") (pin "2") (pinfunction "2_2") (pintype "passive"))
      (node (ref "R989") (pin "1") (pinfunction "1_1") (pintype "passive"))
      (node (ref "TP952") (pin "1") (pinfunction "TP_1") (pintype "passive"))
    )
    (net (code "40") (name "NVCC_BBSM_1P8") (class "Default")
      (node (ref "R903") (pin "1") (pinfunction "1_1") (pintype "passive"))
      (node (ref "R918") (pin "1") (pinfunction "1_1") (pintype "passive"))
      (node (ref "R920") (pin "2") (pinfunction "2_2") (pintype "passive"))
      (node (ref "TP924") (pin "1") (pinfunction "TP_1") (pintype "passive"))
    )
    (net (code "41") (name "NVCC_BBSM_1V8") (class "Default")
      (node (ref "Q901") (pin "1") (pinfunction "GATE_1") (pintype "input"))
      (node (ref "R902") (pin "1") (pinfunction "1_1") (pintype "passive"))
      (node (ref "R919") (pin "1") (pinfunction "1_1") (pintype "passive"))
      (node (ref "R971") (pin "1") (pinfunction "1_1") (pintype "passive"))
      (node (ref "TP922") (pin "1") (pinfunction "TP_1") (pintype "passive"))
      (node (ref "U903") (pin "11") (pinfunction "VIN_2_11") (pintype "input"))
      (node (ref "U903") (pin "3") (pinfunction "VIN_1_3") (pintype "input"))
    )
    (net (code "42") (name "NVCC_SD") (class "Default")
      (node (ref "R929") (pin "1") (pinfunction "1_1") (pintype "passive"))
      (node (ref "R998") (pin "1") (pinfunction "1_1") (pintype "passive"))
      (node (ref "TP934") (pin "1") (pinfunction "TP_1") (pintype "passive"))
    )
    (net (code "43") (name "NVCC_SD2") (class "Default")
      (node (ref "R935") (pin "1") (pinfunction "1_1") (pintype "passive"))
      (node (ref "R998") (pin "2") (pinfunction "2_2") (pintype "passive"))
      (node (ref "TP935") (pin "1") (pinfunction "TP_1") (pintype "passive"))
    )
    (net (code "44") (name "Net-(Q901-DRAIN)") (class "Default")
      (node (ref "D904") (pin "C") (pinfunction "C_C") (pintype "passive"))
      (node (ref "Q901") (pin "3") (pinfunction "DRAIN_3") (pintype "passive"))
    )
    (net (code "45") (name "Net-(TP953-TP)") (class "Default")
      (node (ref "R1010") (pin "2") (pinfunction "2_2") (pintype "passive"))
      (node (ref "R1015") (pin "1") (pinfunction "1_1") (pintype "passive"))
      (node (ref "TP953") (pin "1") (pinfunction "TP_1") (pintype "passive"))
      (node (ref "U914") (pin "3") (pinfunction "DI_3") (pintype "input"))
    )
    (net (code "46") (name "Net-(TP954-TP)") (class "Default")
      (node (ref "R1012") (pin "2") (pinfunction "2_2") (pintype "passive"))
      (node (ref "R1016") (pin "1") (pinfunction "1_1") (pintype "passive"))
      (node (ref "TP954") (pin "1") (pinfunction "TP_1") (pintype "passive"))
      (node (ref "U914") (pin "4") (pinfunction "CLK_4") (pintype "input"))
    )
    (net (code "47") (name "Net-(TP955-TP)") (class "Default")
      (node (ref "R1013") (pin "2") (pinfunction "2_2") (pintype "passive"))
      (node (ref "R1018") (pin "1") (pinfunction "1_1") (pintype "passive"))
      (node (ref "TP955") (pin "1") (pinfunction "TP_1") (pintype "passive"))
      (node (ref "U914") (pin "5") (pinfunction "CS_5") (pintype "input"))
    )
    (net (code "48") (name "Net-(U901-BLEED)") (class "Default")
      (node (ref "R908") (pin "2") (pinfunction "2_2") (pintype "passive"))
      (node (ref "U901") (pin "5") (pinfunction "BLEED_5") (pintype "passive"))
    )
    (net (code "49") (name "Net-(U901-PG)") (class "Default")
      (node (ref "R907") (pin "2") (pinfunction "2_2") (pintype "passive"))
      (node (ref "U901") (pin "6") (pinfunction "PG_6") (pintype "output"))
    )
    (net (code "50") (name "Net-(U902-ADDRSEL)") (class "Default")
      (node (ref "R912") (pin "1") (pinfunction "1_1") (pintype "passive"))
      (node (ref "U902") (pin "6") (pinfunction "ADDRSEL_6") (pintype "bidirectional"))
    )
    (net (code "51") (name "Net-(U902-SENSE1+)") (class "Default")
      (node (ref "C902") (pin "1") (pinfunction "1_1") (pintype "passive"))
      (node (ref "R1044") (pin "2") (pinfunction "2_2") (pintype "passive"))
      (node (ref "R902") (pin "2") (pinfunction "2_2") (pintype "passive"))
      (node (ref "U902") (pin "11") (pinfunction "SENSE1+_11") (pintype "input"))
    )
    (net (code "52") (name "Net-(U902-SENSE1-)") (class "Default")
      (node (ref "C902") (pin "2") (pinfunction "2_2") (pintype "passive"))
      (node (ref "R1045") (pin "2") (pinfunction "2_2") (pintype "passive"))
      (node (ref "R903") (pin "2") (pinfunction "2_2") (pintype "passive"))
      (node (ref "U902") (pin "12") (pinfunction "SENSE1-_12") (pintype "input"))
    )
    (net (code "53") (name "Net-(U902-SENSE2+)") (class "Default")
      (node (ref "C948") (pin "1") (pinfunction "1_1") (pintype "passive"))
      (node (ref "R1008") (pin "2") (pinfunction "2_2") (pintype "passive"))
      (node (ref "U902") (pin "13") (pinfunction "SENSE2+_13") (pintype "input"))
    )
    (net (code "54") (name "Net-(U902-SENSE2-)") (class "Default")
      (node (ref "C948") (pin "2") (pinfunction "2_2") (pintype "passive"))
      (node (ref "R1020") (pin "2") (pinfunction "2_2") (pintype "passive"))
      (node (ref "U902") (pin "14") (pinfunction "SENSE2-_14") (pintype "input"))
    )
    (net (code "55") (name "Net-(U902-SENSE3+)") (class "Default")
      (node (ref "C907") (pin "1") (pinfunction "1_1") (pintype "passive"))
      (node (ref "R1042") (pin "2") (pinfunction "2_2") (pintype "passive"))
      (node (ref "R911") (pin "2") (pinfunction "2_2") (pintype "passive"))
      (node (ref "U902") (pin "8") (pinfunction "SENSE3+_8") (pintype "input"))
    )
    (net (code "56") (name "Net-(U902-SENSE3-)") (class "Default")
      (node (ref "C907") (pin "2") (pinfunction "2_2") (pintype "passive"))
      (node (ref "R1043") (pin "2") (pinfunction "2_2") (pintype "passive"))
      (node (ref "R916") (pin "2") (pinfunction "2_2") (pintype "passive"))
      (node (ref "U902") (pin "7") (pinfunction "SENSE3-_7") (pintype "input"))
    )
    (net (code "57") (name "Net-(U902-SENSE4+)") (class "Default")
      (node (ref "C908") (pin "1") (pinfunction "1_1") (pintype "passive"))
      (node (ref "R917") (pin "2") (pinfunction "2_2") (pintype "passive"))
      (node (ref "U902") (pin "10") (pinfunction "SENSE4+_10") (pintype "input"))
    )
    (net (code "58") (name "Net-(U902-SENSE4-)") (class "Default")
      (node (ref "C908") (pin "2") (pinfunction "2_2") (pintype "passive"))
      (node (ref "R918") (pin "2") (pinfunction "2_2") (pintype "passive"))
      (node (ref "U902") (pin "9") (pinfunction "SENSE4-_9") (pintype "input"))
    )
    (net (code "59") (name "Net-(U902-SLOW{slash}~{ALERT})") (class "Default")
      (node (ref "R913") (pin "1") (pinfunction "1_1") (pintype "passive"))
      (node (ref "R914") (pin "1") (pinfunction "1_1") (pintype "passive"))
      (node (ref "U902") (pin "1") (pinfunction "SLOW/~{ALERT}_1") (pintype "bidirectional"))
    )
    (net (code "60") (name "Net-(U902-~{PWRDN})") (class "Default")
      (node (ref "R915") (pin "1") (pinfunction "1_1") (pintype "passive"))
      (node (ref "U902") (pin "16") (pinfunction "~{PWRDN}_16") (pintype "input"))
    )
    (net (code "61") (name "Net-(U903-CT)") (class "Default")
      (node (ref "C951") (pin "1") (pinfunction "1_1") (pintype "passive"))
      (node (ref "U903") (pin "1") (pinfunction "CT_1") (pintype "output"))
    )
    (net (code "62") (name "Net-(U903-PG)") (class "Default")
      (node (ref "R922") (pin "2") (pinfunction "2_2") (pintype "passive"))
      (node (ref "U903") (pin "7") (pinfunction "PG_7") (pintype "output"))
    )
    (net (code "63") (name "Net-(U904-ADDRSEL)") (class "Default")
      (node (ref "R930") (pin "1") (pinfunction "1_1") (pintype "passive"))
      (node (ref "U904") (pin "6") (pinfunction "ADDRSEL_6") (pintype "bidirectional"))
    )
    (net (code "64") (name "Net-(U904-SENSE1+)") (class "Default")
      (node (ref "C910") (pin "1") (pinfunction "1_1") (pintype "passive"))
      (node (ref "R921") (pin "2") (pinfunction "2_2") (pintype "passive"))
      (node (ref "U904") (pin "11") (pinfunction "SENSE1+_11") (pintype "input"))
    )
    (net (code "65") (name "Net-(U904-SENSE1-)") (class "Default")
      (node (ref "C910") (pin "2") (pinfunction "2_2") (pintype "passive"))
      (node (ref "R923") (pin "2") (pinfunction "2_2") (pintype "passive"))
      (node (ref "U904") (pin "12") (pinfunction "SENSE1-_12") (pintype "input"))
    )
    (net (code "66") (name "Net-(U904-SENSE2+)") (class "Default")
      (node (ref "C917") (pin "1") (pinfunction "1_1") (pintype "passive"))
      (node (ref "R924") (pin "2") (pinfunction "2_2") (pintype "passive"))
      (node (ref "U904") (pin "13") (pinfunction "SENSE2+_13") (pintype "input"))
    )
    (net (code "67") (name "Net-(U904-SENSE2-)") (class "Default")
      (node (ref "C917") (pin "2") (pinfunction "2_2") (pintype "passive"))
      (node (ref "R927") (pin "2") (pinfunction "2_2") (pintype "passive"))
      (node (ref "U904") (pin "14") (pinfunction "SENSE2-_14") (pintype "input"))
    )
    (net (code "68") (name "Net-(U904-SENSE3+)") (class "Default")
      (node (ref "C920") (pin "1") (pinfunction "1_1") (pintype "passive"))
      (node (ref "R929") (pin "2") (pinfunction "2_2") (pintype "passive"))
      (node (ref "U904") (pin "8") (pinfunction "SENSE3+_8") (pintype "input"))
    )
    (net (code "69") (name "Net-(U904-SENSE3-)") (class "Default")
      (node (ref "C920") (pin "2") (pinfunction "2_2") (pintype "passive"))
      (node (ref "R935") (pin "2") (pinfunction "2_2") (pintype "passive"))
      (node (ref "U904") (pin "7") (pinfunction "SENSE3-_7") (pintype "input"))
    )
    (net (code "70") (name "Net-(U904-SENSE4+)") (class "Default")
      (node (ref "C921") (pin "1") (pinfunction "1_1") (pintype "passive"))
      (node (ref "R937") (pin "2") (pinfunction "2_2") (pintype "passive"))
      (node (ref "U904") (pin "10") (pinfunction "SENSE4+_10") (pintype "input"))
    )
    (net (code "71") (name "Net-(U904-SENSE4-)") (class "Default")
      (node (ref "C921") (pin "2") (pinfunction "2_2") (pintype "passive"))
      (node (ref "R939") (pin "2") (pinfunction "2_2") (pintype "passive"))
      (node (ref "U904") (pin "9") (pinfunction "SENSE4-_9") (pintype "input"))
    )
    (net (code "72") (name "Net-(U904-SLOW{slash}~{ALERT})") (class "Default")
      (node (ref "R933") (pin "1") (pinfunction "1_1") (pintype "passive"))
      (node (ref "R934") (pin "1") (pinfunction "1_1") (pintype "passive"))
      (node (ref "U904") (pin "1") (pinfunction "SLOW/~{ALERT}_1") (pintype "bidirectional"))
    )
    (net (code "73") (name "Net-(U904-~{PWRDN})") (class "Default")
      (node (ref "R936") (pin "1") (pinfunction "1_1") (pintype "passive"))
      (node (ref "U904") (pin "16") (pinfunction "~{PWRDN}_16") (pintype "input"))
    )
    (net (code "74") (name "Net-(U905-BP)") (class "Default")
      (node (ref "C919") (pin "1") (pinfunction "1_1") (pintype "passive"))
      (node (ref "U905") (pin "4") (pinfunction "BP_4") (pintype "passive"))
    )
    (net (code "75") (name "Net-(U905-VOUT)") (class "Default")
      (node (ref "C914") (pin "1") (pinfunction "1_1") (pintype "passive"))
      (node (ref "D901") (pin "A") (pinfunction "A_A") (pintype "passive"))
      (node (ref "U905") (pin "5") (pinfunction "VOUT_5") (pintype "passive"))
    )
    (net (code "76") (name "Net-(U906-CT)") (class "Default")
      (node (ref "C952") (pin "1") (pinfunction "1_1") (pintype "passive"))
      (node (ref "U906") (pin "1") (pinfunction "CT_1") (pintype "output"))
    )
    (net (code "77") (name "Net-(U906-PG)") (class "Default")
      (node (ref "R938") (pin "2") (pinfunction "2_2") (pintype "passive"))
      (node (ref "U906") (pin "7") (pinfunction "PG_7") (pintype "output"))
    )
    (net (code "78") (name "Net-(U907-ADDRSEL)") (class "Default")
      (node (ref "R950") (pin "1") (pinfunction "1_1") (pintype "passive"))
      (node (ref "U907") (pin "6") (pinfunction "ADDRSEL_6") (pintype "bidirectional"))
    )
    (net (code "79") (name "Net-(U907-SENSE1+)") (class "Default")
      (node (ref "C924") (pin "1") (pinfunction "1_1") (pintype "passive"))
      (node (ref "R941") (pin "2") (pinfunction "2_2") (pintype "passive"))
      (node (ref "U907") (pin "11") (pinfunction "SENSE1+_11") (pintype "input"))
    )
    (net (code "80") (name "Net-(U907-SENSE1-)") (class "Default")
      (node (ref "C924") (pin "2") (pinfunction "2_2") (pintype "passive"))
      (node (ref "R943") (pin "2") (pinfunction "2_2") (pintype "passive"))
      (node (ref "U907") (pin "12") (pinfunction "SENSE1-_12") (pintype "input"))
    )
    (net (code "81") (name "Net-(U907-SENSE2+)") (class "Default")
      (node (ref "C927") (pin "1") (pinfunction "1_1") (pintype "passive"))
      (node (ref "R945") (pin "2") (pinfunction "2_2") (pintype "passive"))
      (node (ref "U907") (pin "13") (pinfunction "SENSE2+_13") (pintype "input"))
    )
    (net (code "82") (name "Net-(U907-SENSE2-)") (class "Default")
      (node (ref "C927") (pin "2") (pinfunction "2_2") (pintype "passive"))
      (node (ref "R947") (pin "2") (pinfunction "2_2") (pintype "passive"))
      (node (ref "U907") (pin "14") (pinfunction "SENSE2-_14") (pintype "input"))
    )
    (net (code "83") (name "Net-(U907-SENSE3+)") (class "Default")
      (node (ref "C932") (pin "1") (pinfunction "1_1") (pintype "passive"))
      (node (ref "R949") (pin "2") (pinfunction "2_2") (pintype "passive"))
      (node (ref "U907") (pin "8") (pinfunction "SENSE3+_8") (pintype "input"))
    )
    (net (code "84") (name "Net-(U907-SENSE3-)") (class "Default")
      (node (ref "C932") (pin "2") (pinfunction "2_2") (pintype "passive"))
      (node (ref "R958") (pin "2") (pinfunction "2_2") (pintype "passive"))
      (node (ref "U907") (pin "7") (pinfunction "SENSE3-_7") (pintype "input"))
    )
    (net (code "85") (name "Net-(U907-SENSE4+)") (class "Default")
      (node (ref "C949") (pin "1") (pinfunction "1_1") (pintype "passive"))
      (node (ref "R1022") (pin "2") (pinfunction "2_2") (pintype "passive"))
      (node (ref "U907") (pin "10") (pinfunction "SENSE4+_10") (pintype "input"))
    )
    (net (code "86") (name "Net-(U907-SENSE4-)") (class "Default")
      (node (ref "C949") (pin "2") (pinfunction "2_2") (pintype "passive"))
      (node (ref "R1026") (pin "2") (pinfunction "2_2") (pintype "passive"))
      (node (ref "U907") (pin "9") (pinfunction "SENSE4-_9") (pintype "input"))
    )
    (net (code "87") (name "Net-(U907-SLOW{slash}~{ALERT})") (class "Default")
      (node (ref "R955") (pin "1") (pinfunction "1_1") (pintype "passive"))
      (node (ref "R956") (pin "1") (pinfunction "1_1") (pintype "passive"))
      (node (ref "U907") (pin "1") (pinfunction "SLOW/~{ALERT}_1") (pintype "bidirectional"))
    )
    (net (code "88") (name "Net-(U907-~{PWRDN})") (class "Default")
      (node (ref "R959") (pin "1") (pinfunction "1_1") (pintype "passive"))
      (node (ref "U907") (pin "16") (pinfunction "~{PWRDN}_16") (pintype "input"))
    )
    (net (code "89") (name "Net-(U908-CT)") (class "Default")
      (node (ref "C953") (pin "1") (pinfunction "1_1") (pintype "passive"))
      (node (ref "U908") (pin "1") (pinfunction "CT_1") (pintype "output"))
    )
    (net (code "90") (name "Net-(U908-PG)") (class "Default")
      (node (ref "R951") (pin "2") (pinfunction "2_2") (pintype "passive"))
      (node (ref "U908") (pin "7") (pinfunction "PG_7") (pintype "output"))
    )
    (net (code "91") (name "Net-(U909-C0)") (class "Default")
      (node (ref "R969") (pin "1") (pinfunction "1_1") (pintype "passive"))
      (node (ref "R977") (pin "2") (pinfunction "2_2") (pintype "passive"))
      (node (ref "U909") (pin "6") (pinfunction "C0_6") (pintype "bidirectional"))
    )
    (net (code "92") (name "Net-(U909-C1)") (class "Default")
      (node (ref "R970") (pin "1") (pinfunction "1_1") (pintype "passive"))
      (node (ref "R976") (pin "2") (pinfunction "2_2") (pintype "passive"))
      (node (ref "U909") (pin "7") (pinfunction "C1_7") (pintype "bidirectional"))
    )
    (net (code "93") (name "Net-(U909-C2)") (class "Default")
      (node (ref "R972") (pin "1") (pinfunction "1_1") (pintype "passive"))
      (node (ref "R975") (pin "2") (pinfunction "2_2") (pintype "passive"))
      (node (ref "U909") (pin "8") (pinfunction "C2_8") (pintype "bidirectional"))
    )
    (net (code "94") (name "Net-(U909-C3)") (class "Default")
      (node (ref "R1034") (pin "1") (pinfunction "1_1") (pintype "passive"))
      (node (ref "R1037") (pin "2") (pinfunction "2_2") (pintype "passive"))
      (node (ref "U909") (pin "9") (pinfunction "C3_9") (pintype "bidirectional"))
    )
    (net (code "95") (name "Net-(U909-C4)") (class "Default")
      (node (ref "R1035") (pin "1") (pinfunction "1_1") (pintype "passive"))
      (node (ref "R1036") (pin "2") (pinfunction "2_2") (pintype "passive"))
      (node (ref "U909") (pin "10") (pinfunction "C4_10") (pintype "bidirectional"))
    )
    (net (code "96") (name "Net-(U909-R0)") (class "Default")
      (node (ref "R960") (pin "1") (pinfunction "1_1") (pintype "passive"))
      (node (ref "R982") (pin "1") (pinfunction "1_1") (pintype "passive"))
      (node (ref "U909") (pin "5") (pinfunction "R0_5") (pintype "bidirectional"))
    )
    (net (code "97") (name "Net-(U909-R1)") (class "Default")
      (node (ref "R962") (pin "1") (pinfunction "1_1") (pintype "passive"))
      (node (ref "R981") (pin "1") (pinfunction "1_1") (pintype "passive"))
      (node (ref "U909") (pin "4") (pinfunction "R1_4") (pintype "bidirectional"))
    )
    (net (code "98") (name "Net-(U909-R2)") (class "Default")
      (node (ref "R963") (pin "1") (pinfunction "1_1") (pintype "passive"))
      (node (ref "R980") (pin "1") (pinfunction "1_1") (pintype "passive"))
      (node (ref "U909") (pin "3") (pinfunction "R2_3") (pintype "bidirectional"))
    )
    (net (code "99") (name "Net-(U909-R3)") (class "Default")
      (node (ref "R964") (pin "1") (pinfunction "1_1") (pintype "passive"))
      (node (ref "R979") (pin "1") (pinfunction "1_1") (pintype "passive"))
      (node (ref "U909") (pin "2") (pinfunction "R3_2") (pintype "bidirectional"))
    )
    (net (code "100") (name "Net-(U909-R4)") (class "Default")
      (node (ref "R966") (pin "1") (pinfunction "1_1") (pintype "passive"))
      (node (ref "R978") (pin "1") (pinfunction "1_1") (pintype "passive"))
      (node (ref "U909") (pin "1") (pinfunction "R4_1") (pintype "bidirectional"))
    )
    (net (code "101") (name "Net-(U909-~{INT})") (class "Default")
      (node (ref "R953") (pin "2") (pinfunction "2_2") (pintype "passive"))
      (node (ref "R961") (pin "2") (pinfunction "2_2") (pintype "passive"))
      (node (ref "U909") (pin "16") (pinfunction "~{INT}_16") (pintype "output"))
    )
    (net (code "102") (name "Net-(U909-~{RST}{slash}R5)") (class "Default")
      (node (ref "D903") (pin "A") (pinfunction "A_A") (pintype "passive"))
      (node (ref "D904") (pin "A") (pinfunction "A_A") (pintype "passive"))
      (node (ref "R952") (pin "2") (pinfunction "2_2") (pintype "passive"))
      (node (ref "U909") (pin "11") (pinfunction "~{RST}/R5_11") (pintype "input"))
    )
    (net (code "103") (name "Net-(U910-CT)") (class "Default")
      (node (ref "C954") (pin "1") (pinfunction "1_1") (pintype "passive"))
      (node (ref "U910") (pin "1") (pinfunction "CT_1") (pintype "output"))
    )
    (net (code "104") (name "Net-(U910-PG)") (class "Default")
      (node (ref "R985") (pin "2") (pinfunction "2_2") (pintype "passive"))
      (node (ref "U910") (pin "7") (pinfunction "PG_7") (pintype "output"))
    )
    (net (code "105") (name "Net-(U911-ADDRSEL)") (class "Default")
      (node (ref "R992") (pin "1") (pinfunction "1_1") (pintype "passive"))
      (node (ref "U911") (pin "6") (pinfunction "ADDRSEL_6") (pintype "bidirectional"))
    )
    (net (code "106") (name "Net-(U911-SENSE1+)") (class "Default")
      (node (ref "C936") (pin "1") (pinfunction "1_1") (pintype "passive"))
      (node (ref "R983") (pin "2") (pinfunction "2_2") (pintype "passive"))
      (node (ref "U911") (pin "11") (pinfunction "SENSE1+_11") (pintype "input"))
    )
    (net (code "107") (name "Net-(U911-SENSE1-)") (class "Default")
      (node (ref "C936") (pin "2") (pinfunction "2_2") (pintype "passive"))
      (node (ref "R984") (pin "2") (pinfunction "2_2") (pintype "passive"))
      (node (ref "U911") (pin "12") (pinfunction "SENSE1-_12") (pintype "input"))
    )
    (net (code "108") (name "Net-(U911-SENSE2+)") (class "Default")
      (node (ref "C939") (pin "1") (pinfunction "1_1") (pintype "passive"))
      (node (ref "R987") (pin "2") (pinfunction "2_2") (pintype "passive"))
      (node (ref "U911") (pin "13") (pinfunction "SENSE2+_13") (pintype "input"))
    )
    (net (code "109") (name "Net-(U911-SENSE2-)") (class "Default")
      (node (ref "C939") (pin "2") (pinfunction "2_2") (pintype "passive"))
      (node (ref "R989") (pin "2") (pinfunction "2_2") (pintype "passive"))
      (node (ref "U911") (pin "14") (pinfunction "SENSE2-_14") (pintype "input"))
    )
    (net (code "110") (name "Net-(U911-SENSE3+)") (class "Default")
      (node (ref "C940") (pin "1") (pinfunction "1_1") (pintype "passive"))
      (node (ref "R991") (pin "2") (pinfunction "2_2") (pintype "passive"))
      (node (ref "U911") (pin "8") (pinfunction "SENSE3+_8") (pintype "input"))
    )
    (net (code "111") (name "Net-(U911-SENSE3-)") (class "Default")
      (node (ref "C940") (pin "2") (pinfunction "2_2") (pintype "passive"))
      (node (ref "R996") (pin "2") (pinfunction "2_2") (pintype "passive"))
      (node (ref "U911") (pin "7") (pinfunction "SENSE3-_7") (pintype "input"))
    )
    (net (code "112") (name "Net-(U911-SENSE4+)") (class "Default")
      (node (ref "C941") (pin "1") (pinfunction "1_1") (pintype "passive"))
      (node (ref "R997") (pin "2") (pinfunction "2_2") (pintype "passive"))
      (node (ref "U911") (pin "10") (pinfunction "SENSE4+_10") (pintype "input"))
    )
    (net (code "113") (name "Net-(U911-SENSE4-)") (class "Default")
      (node (ref "C941") (pin "2") (pinfunction "2_2") (pintype "passive"))
      (node (ref "R1000") (pin "2") (pinfunction "2_2") (pintype "passive"))
      (node (ref "U911") (pin "9") (pinfunction "SENSE4-_9") (pintype "input"))
    )
    (net (code "114") (name "Net-(U911-SLOW{slash}~{ALERT})") (class "Default")
      (node (ref "R993") (pin "1") (pinfunction "1_1") (pintype "passive"))
      (node (ref "R994") (pin "1") (pinfunction "1_1") (pintype "passive"))
      (node (ref "U911") (pin "1") (pinfunction "SLOW/~{ALERT}_1") (pintype "bidirectional"))
    )
    (net (code "115") (name "Net-(U911-~{PWRDN})") (class "Default")
      (node (ref "R995") (pin "1") (pinfunction "1_1") (pintype "passive"))
      (node (ref "U911") (pin "16") (pinfunction "~{PWRDN}_16") (pintype "input"))
    )
    (net (code "116") (name "Net-(U912-ADDRSEL)") (class "Default")
      (node (ref "R1023") (pin "1") (pinfunction "1_1") (pintype "passive"))
      (node (ref "U912") (pin "6") (pinfunction "ADDRSEL_6") (pintype "bidirectional"))
    )
    (net (code "117") (name "Net-(U912-SENSE1+)") (class "Default")
      (node (ref "C945") (pin "1") (pinfunction "1_1") (pintype "passive"))
      (node (ref "R1005") (pin "2") (pinfunction "2_2") (pintype "passive"))
      (node (ref "U912") (pin "11") (pinfunction "SENSE1+_11") (pintype "input"))
    )
    (net (code "118") (name "Net-(U912-SENSE1-)") (class "Default")
      (node (ref "C945") (pin "2") (pinfunction "2_2") (pintype "passive"))
      (node (ref "R1006") (pin "2") (pinfunction "2_2") (pintype "passive"))
      (node (ref "U912") (pin "12") (pinfunction "SENSE1-_12") (pintype "input"))
    )
    (net (code "119") (name "Net-(U912-SENSE2+)") (class "Default")
      (node (ref "C905") (pin "1") (pinfunction "1_1") (pintype "passive"))
      (node (ref "R905") (pin "2") (pinfunction "2_2") (pintype "passive"))
      (node (ref "U912") (pin "13") (pinfunction "SENSE2+_13") (pintype "input"))
    )
    (net (code "120") (name "Net-(U912-SENSE2-)") (class "Default")
      (node (ref "C905") (pin "2") (pinfunction "2_2") (pintype "passive"))
      (node (ref "R909") (pin "2") (pinfunction "2_2") (pintype "passive"))
      (node (ref "U912") (pin "14") (pinfunction "SENSE2-_14") (pintype "input"))
    )
    (net (code "121") (name "Net-(U912-SENSE3+)") (class "Default")
      (node (ref "C933") (pin "1") (pinfunction "1_1") (pintype "passive"))
      (node (ref "R957") (pin "2") (pinfunction "2_2") (pintype "passive"))
      (node (ref "U912") (pin "8") (pinfunction "SENSE3+_8") (pintype "input"))
    )
    (net (code "122") (name "Net-(U912-SENSE3-)") (class "Default")
      (node (ref "C933") (pin "2") (pinfunction "2_2") (pintype "passive"))
      (node (ref "R967") (pin "2") (pinfunction "2_2") (pintype "passive"))
      (node (ref "U912") (pin "7") (pinfunction "SENSE3-_7") (pintype "input"))
    )
    (net (code "123") (name "Net-(U912-SENSE4+)") (class "Default")
      (node (ref "C950") (pin "1") (pinfunction "1_1") (pintype "passive"))
      (node (ref "R1028") (pin "2") (pinfunction "2_2") (pintype "passive"))
      (node (ref "U912") (pin "10") (pinfunction "SENSE4+_10") (pintype "input"))
    )
    (net (code "124") (name "Net-(U912-SENSE4-)") (class "Default")
      (node (ref "C950") (pin "2") (pinfunction "2_2") (pintype "passive"))
      (node (ref "R1029") (pin "2") (pinfunction "2_2") (pintype "passive"))
      (node (ref "U912") (pin "9") (pinfunction "SENSE4-_9") (pintype "input"))
    )
    (net (code "125") (name "Net-(U912-SLOW{slash}~{ALERT})") (class "Default")
      (node (ref "R1024") (pin "1") (pinfunction "1_1") (pintype "passive"))
      (node (ref "R1025") (pin "1") (pinfunction "1_1") (pintype "passive"))
      (node (ref "U912") (pin "1") (pinfunction "SLOW/~{ALERT}_1") (pintype "bidirectional"))
    )
    (net (code "126") (name "Net-(U912-~{PWRDN})") (class "Default")
      (node (ref "R1027") (pin "1") (pinfunction "1_1") (pintype "passive"))
      (node (ref "U912") (pin "16") (pinfunction "~{PWRDN}_16") (pintype "input"))
    )
    (net (code "127") (name "Net-(U913-SCL)") (class "Default")
      (node (ref "R1033") (pin "2") (pinfunction "2_2") (pintype "passive"))
      (node (ref "U913") (pin "2") (pinfunction "SCL_2") (pintype "input"))
    )
    (net (code "128") (name "Net-(U913-SDA)") (class "Default")
      (node (ref "R1032") (pin "2") (pinfunction "2_2") (pintype "passive"))
      (node (ref "U913") (pin "1") (pinfunction "SDA_1") (pintype "bidirectional"))
    )
    (net (code "129") (name "Net-(U914-DO)") (class "Default")
      (node (ref "R1010") (pin "1") (pinfunction "1_1") (pintype "passive"))
      (node (ref "R1011") (pin "2") (pinfunction "2_2") (pintype "passive"))
      (node (ref "U914") (pin "1") (pinfunction "DO_1") (pintype "output"))
    )
    (net (code "130") (name "POR_B") (class "Default")
      (node (ref "Q901") (pin "2") (pinfunction "SOURCE_2") (pintype "passive"))
      (node (ref "R971") (pin "2") (pinfunction "2_2") (pintype "passive"))
    )
    (net (code "131") (name "S1_CPU_VDD2_DDR") (class "Default")
      (node (ref "R937") (pin "1") (pinfunction "1_1") (pintype "passive"))
      (node (ref "R942") (pin "2") (pinfunction "2_2") (pintype "passive"))
      (node (ref "R944") (pin "1") (pinfunction "1_1") (pintype "passive"))
      (node (ref "TP929") (pin "1") (pinfunction "TP_1") (pintype "passive"))
      (node (ref "U908") (pin "10") (pinfunction "VOUT_10") (pintype "output"))
    )
    (net (code "132") (name "S1_CPU_VDDQ_DDR") (class "Default")
      (node (ref "R945") (pin "1") (pinfunction "1_1") (pintype "passive"))
      (node (ref "R973") (pin "2") (pinfunction "2_2") (pintype "passive"))
      (node (ref "R974") (pin "1") (pinfunction "1_1") (pintype "passive"))
      (node (ref "TP932") (pin "1") (pinfunction "TP_1") (pintype "passive"))
      (node (ref "U910") (pin "10") (pinfunction "VOUT_10") (pintype "output"))
    )
    (net (code "133") (name "S1_NVCC_BBSM_1V8") (class "Default")
      (node (ref "R917") (pin "1") (pinfunction "1_1") (pintype "passive"))
      (node (ref "R919") (pin "2") (pinfunction "2_2") (pintype "passive"))
      (node (ref "R920") (pin "1") (pinfunction "1_1") (pintype "passive"))
      (node (ref "TP923") (pin "1") (pinfunction "TP_1") (pintype "passive"))
      (node (ref "U903") (pin "10") (pinfunction "VOUT_10") (pintype "output"))
    )
    (net (code "134") (name "S1_VDD_SOC_0V8") (class "Default")
      (node (ref "R924") (pin "1") (pinfunction "1_1") (pintype "passive"))
      (node (ref "R931") (pin "2") (pinfunction "2_2") (pintype "passive"))
      (node (ref "R932") (pin "1") (pinfunction "1_1") (pintype "passive"))
      (node (ref "TP926") (pin "1") (pinfunction "TP_1") (pintype "passive"))
      (node (ref "U906") (pin "10") (pinfunction "VOUT_10") (pintype "output"))
    )
    (net (code "135") (name "S1_VSYS_5V") (class "Default")
      (node (ref "R901") (pin "2") (pinfunction "2_2") (pintype "passive"))
      (node (ref "R904") (pin "1") (pinfunction "1_1") (pintype "passive"))
      (node (ref "R908") (pin "1") (pinfunction "1_1") (pintype "passive"))
      (node (ref "R983") (pin "1") (pinfunction "1_1") (pintype "passive"))
      (node (ref "TP920") (pin "1") (pinfunction "TP_1") (pintype "passive"))
      (node (ref "U901") (pin "7") (pinfunction "VOUT_7") (pintype "output"))
    )
    (net (code "136") (name "VDD2_DDR") (class "Default")
      (node (ref "R939") (pin "1") (pinfunction "1_1") (pintype "passive"))
      (node (ref "R944") (pin "2") (pinfunction "2_2") (pintype "passive"))
      (node (ref "R958") (pin "1") (pinfunction "1_1") (pintype "passive"))
      (node (ref "TP930") (pin "1") (pinfunction "TP_1") (pintype "passive"))
    )
    (net (code "137") (name "VDDQ_DDR") (class "Default")
      (node (ref "R943") (pin "1") (pinfunction "1_1") (pintype "passive"))
      (node (ref "R947") (pin "1") (pinfunction "1_1") (pintype "passive"))
      (node (ref "R974") (pin "2") (pinfunction "2_2") (pintype "passive"))
      (node (ref "TP933") (pin "1") (pinfunction "TP_1") (pintype "passive"))
    )
    (net (code "138") (name "VDD_1P8") (class "Default")
      (node (ref "R1041") (pin "1") (pinfunction "1_1") (pintype "passive"))
      (node (ref "R1044") (pin "1") (pinfunction "1_1") (pintype "passive"))
      (node (ref "TP959") (pin "1") (pinfunction "TP_1") (pintype "passive"))
    )
    (net (code "139") (name "VDD_1V8") (class "Default")
      (node (ref "R1004") (pin "1") (pinfunction "1_1") (pintype "passive"))
      (node (ref "R1005") (pin "1") (pinfunction "1_1") (pintype "passive"))
      (node (ref "R1014") (pin "1") (pinfunction "1_1") (pintype "passive"))
      (node (ref "R1028") (pin "1") (pinfunction "1_1") (pintype "passive"))
      (node (ref "R1041") (pin "2") (pinfunction "2_2") (pintype "passive"))
      (node (ref "R1045") (pin "1") (pinfunction "1_1") (pintype "passive"))
      (node (ref "TP942") (pin "1") (pinfunction "TP_1") (pintype "passive"))
      (node (ref "TP946") (pin "1") (pinfunction "TP_1") (pintype "passive"))
      (node (ref "TP960") (pin "1") (pinfunction "TP_1") (pintype "passive"))
    )
    (net (code "140") (name "VDD_3P3") (class "Default")
      (node (ref "R1040") (pin "1") (pinfunction "1_1") (pintype "passive"))
      (node (ref "R1042") (pin "1") (pinfunction "1_1") (pintype "passive"))
      (node (ref "TP957") (pin "1") (pinfunction "TP_1") (pintype "passive"))
    )
    (net (code "141") (name "VDD_3V3") (class "Default")
      (node (ref "R1002") (pin "1") (pinfunction "1_1") (pintype "passive"))
      (node (ref "R1003") (pin "1") (pinfunction "1_1") (pintype "passive"))
      (node (ref "R1040") (pin "2") (pinfunction "2_2") (pintype "passive"))
      (node (ref "R1043") (pin "1") (pinfunction "1_1") (pintype "passive"))
      (node (ref "R987") (pin "1") (pinfunction "1_1") (pintype "passive"))
      (node (ref "R991") (pin "1") (pinfunction "1_1") (pintype "passive"))
      (node (ref "TP940") (pin "1") (pinfunction "TP_1") (pintype "passive"))
      (node (ref "TP956") (pin "1") (pinfunction "TP_1") (pintype "passive"))
      (node (ref "TP958") (pin "1") (pinfunction "TP_1") (pintype "passive"))
    )
    (net (code "142") (name "VDD_ANA_0P8") (class "Default")
      (node (ref "R1000") (pin "1") (pinfunction "1_1") (pintype "passive"))
      (node (ref "R999") (pin "2") (pinfunction "2_2") (pintype "passive"))
      (node (ref "TP937") (pin "1") (pinfunction "TP_1") (pintype "passive"))
    )
    (net (code "143") (name "VDD_ANA_0V8") (class "Default")
      (node (ref "R997") (pin "1") (pinfunction "1_1") (pintype "passive"))
      (node (ref "R999") (pin "1") (pinfunction "1_1") (pintype "passive"))
      (node (ref "TP936") (pin "1") (pinfunction "TP_1") (pintype "passive"))
    )
    (net (code "144") (name "VDD_ANA_1P8") (class "Default")
      (node (ref "R1001") (pin "2") (pinfunction "2_2") (pintype "passive"))
      (node (ref "R909") (pin "1") (pinfunction "1_1") (pintype "passive"))
      (node (ref "TP939") (pin "1") (pinfunction "TP_1") (pintype "passive"))
    )
    (net (code "145") (name "VDD_ANA_1V8") (class "Default")
      (node (ref "R1001") (pin "1") (pinfunction "1_1") (pintype "passive"))
      (node (ref "R905") (pin "1") (pinfunction "1_1") (pintype "passive"))
      (node (ref "TP938") (pin "1") (pinfunction "TP_1") (pintype "passive"))
    )
    (net (code "146") (name "VDD_SOC") (class "Default")
      (node (ref "R1020") (pin "1") (pinfunction "1_1") (pintype "passive"))
      (node (ref "R927") (pin "1") (pinfunction "1_1") (pintype "passive"))
      (node (ref "R932") (pin "2") (pinfunction "2_2") (pintype "passive"))
      (node (ref "TP927") (pin "1") (pinfunction "TP_1") (pintype "passive"))
    )
    (net (code "147") (name "VDD_SOC_0V8") (class "Default")
      (node (ref "R1008") (pin "1") (pinfunction "1_1") (pintype "passive"))
      (node (ref "R931") (pin "1") (pinfunction "1_1") (pintype "passive"))
      (node (ref "TP925") (pin "1") (pinfunction "TP_1") (pintype "passive"))
      (node (ref "U906") (pin "11") (pinfunction "VIN_2_11") (pintype "input"))
      (node (ref "U906") (pin "3") (pinfunction "VIN_1_3") (pintype "input"))
    )
    (net (code "148") (name "VDD_USB_3P3") (class "Default")
      (node (ref "R1002") (pin "2") (pinfunction "2_2") (pintype "passive"))
      (node (ref "R996") (pin "1") (pinfunction "1_1") (pintype "passive"))
      (node (ref "TP941") (pin "1") (pinfunction "TP_1") (pintype "passive"))
    )
    (net (code "149") (name "VLS_3V3") (class "Default")
      (node (ref "C901") (pin "1") (pinfunction "1_1") (pintype "passive"))
      (node (ref "C906") (pin "1") (pinfunction "1_1") (pintype "passive"))
      (node (ref "C909") (pin "1") (pinfunction "1_1") (pintype "passive"))
      (node (ref "C912") (pin "1") (pinfunction "1_1") (pintype "passive"))
      (node (ref "C922") (pin "1") (pinfunction "1_1") (pintype "passive"))
      (node (ref "C923") (pin "1") (pinfunction "1_1") (pintype "passive"))
      (node (ref "C930") (pin "1") (pinfunction "1_1") (pintype "passive"))
      (node (ref "C931") (pin "1") (pinfunction "1_1") (pintype "passive"))
      (node (ref "C935") (pin "1") (pinfunction "1_1") (pintype "passive"))
      (node (ref "C938") (pin "1") (pinfunction "1_1") (pintype "passive"))
      (node (ref "D901") (pin "C") (pinfunction "C_C") (pintype "passive"))
      (node (ref "D902") (pin "C") (pinfunction "C_C") (pintype "passive"))
      (node (ref "R907") (pin "1") (pinfunction "1_1") (pintype "passive"))
      (node (ref "R922") (pin "1") (pinfunction "1_1") (pintype "passive"))
      (node (ref "R938") (pin "1") (pinfunction "1_1") (pintype "passive"))
      (node (ref "R951") (pin "1") (pinfunction "1_1") (pintype "passive"))
      (node (ref "R985") (pin "1") (pinfunction "1_1") (pintype "passive"))
      (node (ref "TP903") (pin "1") (pinfunction "TP_1") (pintype "passive"))
      (node (ref "U901") (pin "3") (pinfunction "VCC_3") (pintype "power_in"))
      (node (ref "U903") (pin "4") (pinfunction "VBIAS_4") (pintype "power_in"))
      (node (ref "U906") (pin "4") (pinfunction "VBIAS_4") (pintype "power_in"))
      (node (ref "U908") (pin "4") (pinfunction "VBIAS_4") (pintype "power_in"))
      (node (ref "U910") (pin "4") (pinfunction "VBIAS_4") (pintype "power_in"))
    )
    (net (code "150") (name "VMEAS_3V3") (class "Default")
      (node (ref "C903") (pin "1") (pinfunction "1_1") (pintype "passive"))
      (node (ref "C904") (pin "1") (pinfunction "1_1") (pintype "passive"))
      (node (ref "C911") (pin "1") (pinfunction "1_1") (pintype "passive"))
      (node (ref "C913") (pin "1") (pinfunction "1_1") (pintype "passive"))
      (node (ref "C915") (pin "1") (pinfunction "1_1") (pintype "passive"))
      (node (ref "C916") (pin "1") (pinfunction "1_1") (pintype "passive"))
      (node (ref "C925") (pin "1") (pinfunction "1_1") (pintype "passive"))
      (node (ref "C926") (pin "1") (pinfunction "1_1") (pintype "passive"))
      (node (ref "C928") (pin "1") (pinfunction "1_1") (pintype "passive"))
      (node (ref "C929") (pin "1") (pinfunction "1_1") (pintype "passive"))
      (node (ref "C934") (pin "1") (pinfunction "1_1") (pintype "passive"))
      (node (ref "C937") (pin "1") (pinfunction "1_1") (pintype "passive"))
      (node (ref "C942") (pin "1") (pinfunction "1_1") (pintype "passive"))
      (node (ref "C943") (pin "1") (pinfunction "1_1") (pintype "passive"))
      (node (ref "C944") (pin "1") (pinfunction "1_1") (pintype "passive"))
      (node (ref "C946") (pin "1") (pinfunction "1_1") (pintype "passive"))
      (node (ref "C947") (pin "1") (pinfunction "1_1") (pintype "passive"))
      (node (ref "D902") (pin "A") (pinfunction "A_A") (pintype "passive"))
      (node (ref "J901") (pin "1") (pinfunction "A1_1") (pintype "passive"))
      (node (ref "J901") (pin "11") (pinfunction "A6_11") (pintype "passive"))
      (node (ref "R1009") (pin "1") (pinfunction "1_1") (pintype "passive"))
      (node (ref "R1011") (pin "1") (pinfunction "1_1") (pintype "passive"))
      (node (ref "R1012") (pin "1") (pinfunction "1_1") (pintype "passive"))
      (node (ref "R1013") (pin "1") (pinfunction "1_1") (pintype "passive"))
      (node (ref "R1025") (pin "2") (pinfunction "2_2") (pintype "passive"))
      (node (ref "R1027") (pin "2") (pinfunction "2_2") (pintype "passive"))
      (node (ref "R1036") (pin "1") (pinfunction "1_1") (pintype "passive"))
      (node (ref "R1037") (pin "1") (pinfunction "1_1") (pintype "passive"))
      (node (ref "R914") (pin "2") (pinfunction "2_2") (pintype "passive"))
      (node (ref "R915") (pin "2") (pinfunction "2_2") (pintype "passive"))
      (node (ref "R934") (pin "2") (pinfunction "2_2") (pintype "passive"))
      (node (ref "R936") (pin "2") (pinfunction "2_2") (pintype "passive"))
      (node (ref "R952") (pin "1") (pinfunction "1_1") (pintype "passive"))
      (node (ref "R953") (pin "1") (pinfunction "1_1") (pintype "passive"))
      (node (ref "R956") (pin "2") (pinfunction "2_2") (pintype "passive"))
      (node (ref "R959") (pin "2") (pinfunction "2_2") (pintype "passive"))
      (node (ref "R975") (pin "1") (pinfunction "1_1") (pintype "passive"))
      (node (ref "R976") (pin "1") (pinfunction "1_1") (pintype "passive"))
      (node (ref "R977") (pin "1") (pinfunction "1_1") (pintype "passive"))
      (node (ref "R994") (pin "2") (pinfunction "2_2") (pintype "passive"))
      (node (ref "R995") (pin "2") (pinfunction "2_2") (pintype "passive"))
      (node (ref "TP902") (pin "1") (pinfunction "TP_1") (pintype "passive"))
      (node (ref "U902") (pin "15") (pinfunction "VDD_I/O_15") (pintype "power_in"))
      (node (ref "U902") (pin "2") (pinfunction "VDD_2") (pintype "power_in"))
      (node (ref "U904") (pin "15") (pinfunction "VDD_I/O_15") (pintype "power_in"))
      (node (ref "U904") (pin "2") (pinfunction "VDD_2") (pintype "power_in"))
      (node (ref "U907") (pin "15") (pinfunction "VDD_I/O_15") (pintype "power_in"))
      (node (ref "U907") (pin "2") (pinfunction "VDD_2") (pintype "power_in"))
      (node (ref "U909") (pin "12") (pinfunction "VDD_12") (pintype "power_in"))
      (node (ref "U911") (pin "15") (pinfunction "VDD_I/O_15") (pintype "power_in"))
      (node (ref "U911") (pin "2") (pinfunction "VDD_2") (pintype "power_in"))
      (node (ref "U912") (pin "15") (pinfunction "VDD_I/O_15") (pintype "power_in"))
      (node (ref "U912") (pin "2") (pinfunction "VDD_2") (pintype "power_in"))
      (node (ref "U913") (pin "8") (pinfunction "VCC_8") (pintype "power_in"))
      (node (ref "U914") (pin "6") (pinfunction "VCC_6") (pintype "power_in"))
    )
    (net (code "151") (name "VSD2_3V3") (class "Default")
      (node (ref "R1031") (pin "2") (pinfunction "2_2") (pintype "passive"))
      (node (ref "R967") (pin "1") (pinfunction "1_1") (pintype "passive"))
      (node (ref "TP945") (pin "1") (pinfunction "TP_1") (pintype "passive"))
    )
    (net (code "152") (name "VSD_3V3") (class "Default")
      (node (ref "R1031") (pin "1") (pinfunction "1_1") (pintype "passive"))
      (node (ref "R957") (pin "1") (pinfunction "1_1") (pintype "passive"))
      (node (ref "TP944") (pin "1") (pinfunction "TP_1") (pintype "passive"))
    )
    (net (code "153") (name "VSYS_5V") (class "Default")
      (node (ref "R904") (pin "2") (pinfunction "2_2") (pintype "passive"))
      (node (ref "R916") (pin "1") (pinfunction "1_1") (pintype "passive"))
      (node (ref "R984") (pin "1") (pinfunction "1_1") (pintype "passive"))
      (node (ref "TP921") (pin "1") (pinfunction "TP_1") (pintype "passive"))
    )
    (net (code "154") (name "unconnected-(J901-B4-Pad8)") (class "Default")
      (node (ref "J901") (pin "8") (pinfunction "B4_8") (pintype "passive"))
    )
    (net (code "155") (name "unconnected-(U903-NC-Pad2)") (class "Default")
      (node (ref "U903") (pin "2") (pinfunction "NC_2") (pintype "passive"))
    )
    (net (code "156") (name "unconnected-(U906-NC-Pad2)") (class "Default")
      (node (ref "U906") (pin "2") (pinfunction "NC_2") (pintype "passive"))
    )
    (net (code "157") (name "unconnected-(U908-NC-Pad2)") (class "Default")
      (node (ref "U908") (pin "2") (pinfunction "NC_2") (pintype "passive"))
    )
    (net (code "158") (name "unconnected-(U910-NC-Pad2)") (class "Default")
      (node (ref "U910") (pin "2") (pinfunction "NC_2") (pintype "passive"))
    )
  )
)
